# 2014_FDP_STRATEGIE.net
KiCad netlist of a schematic drawn in Altium Designer
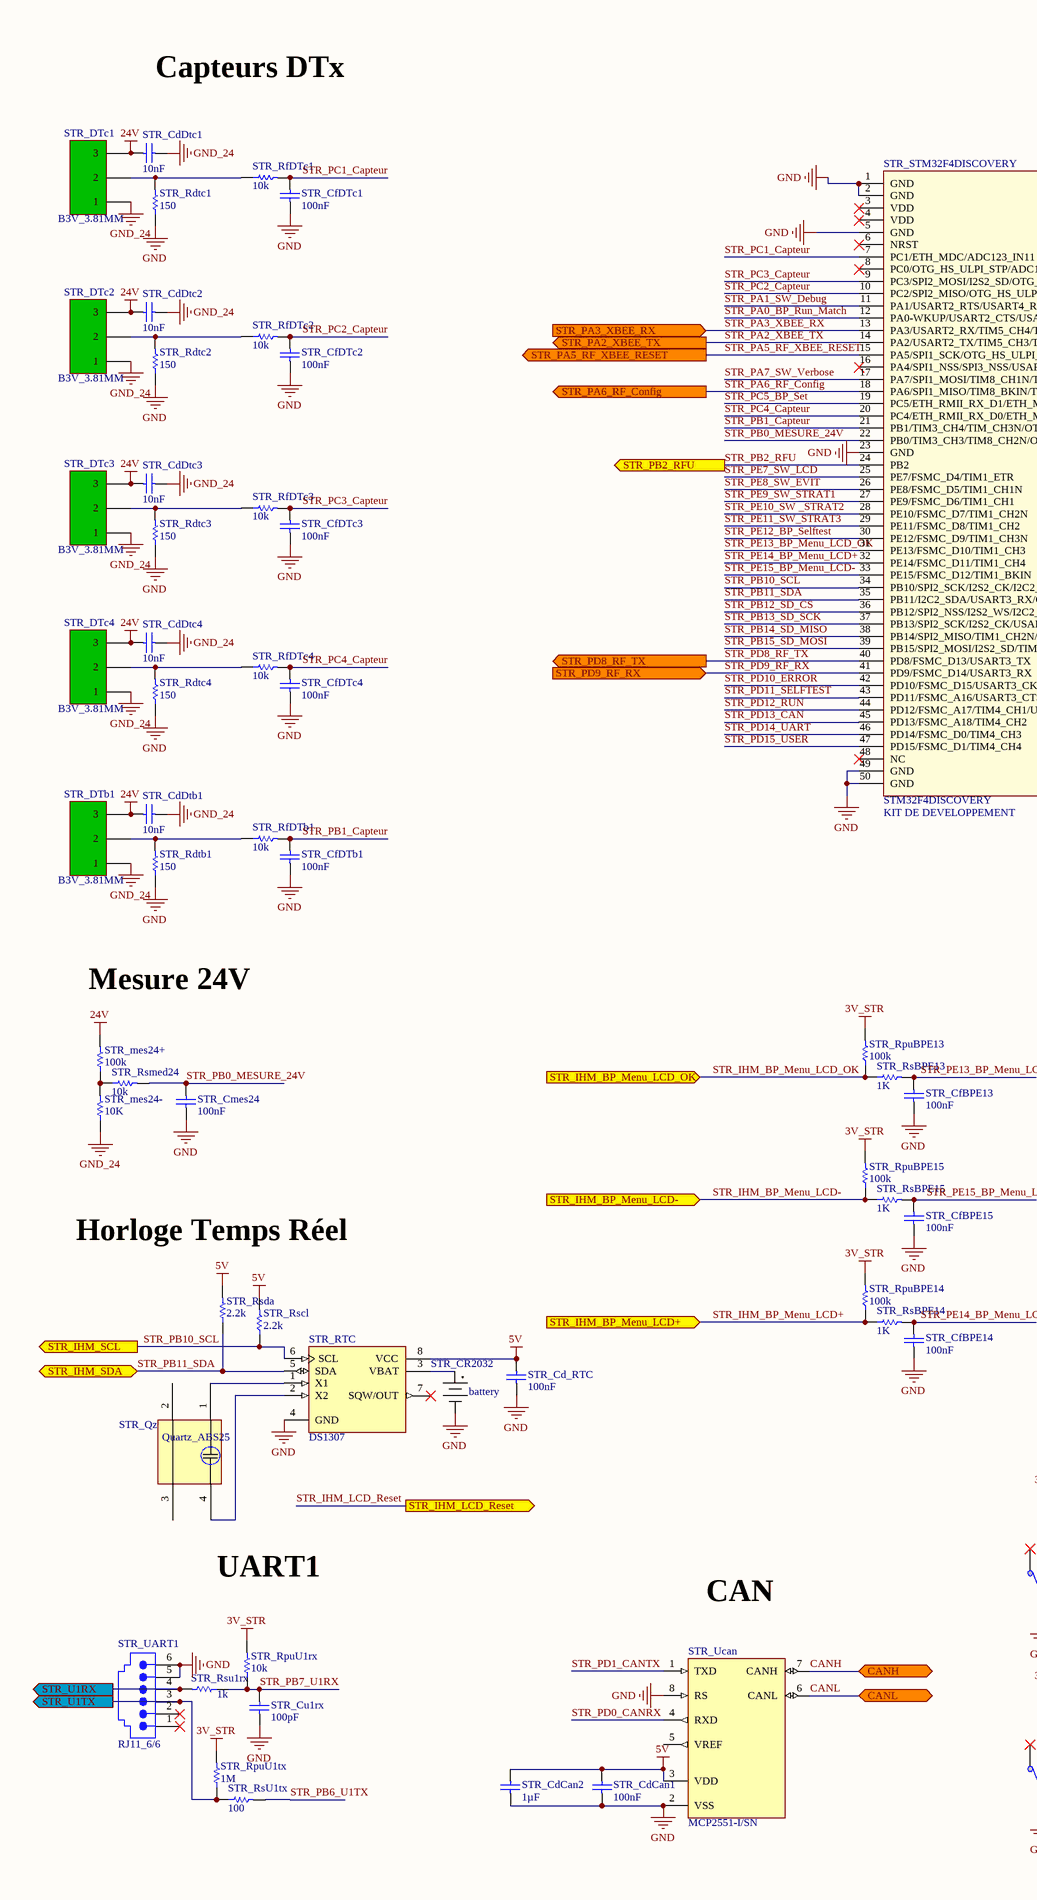
[diagram p0: 2014_FDP_STRATEGIE.SchDoc, left]
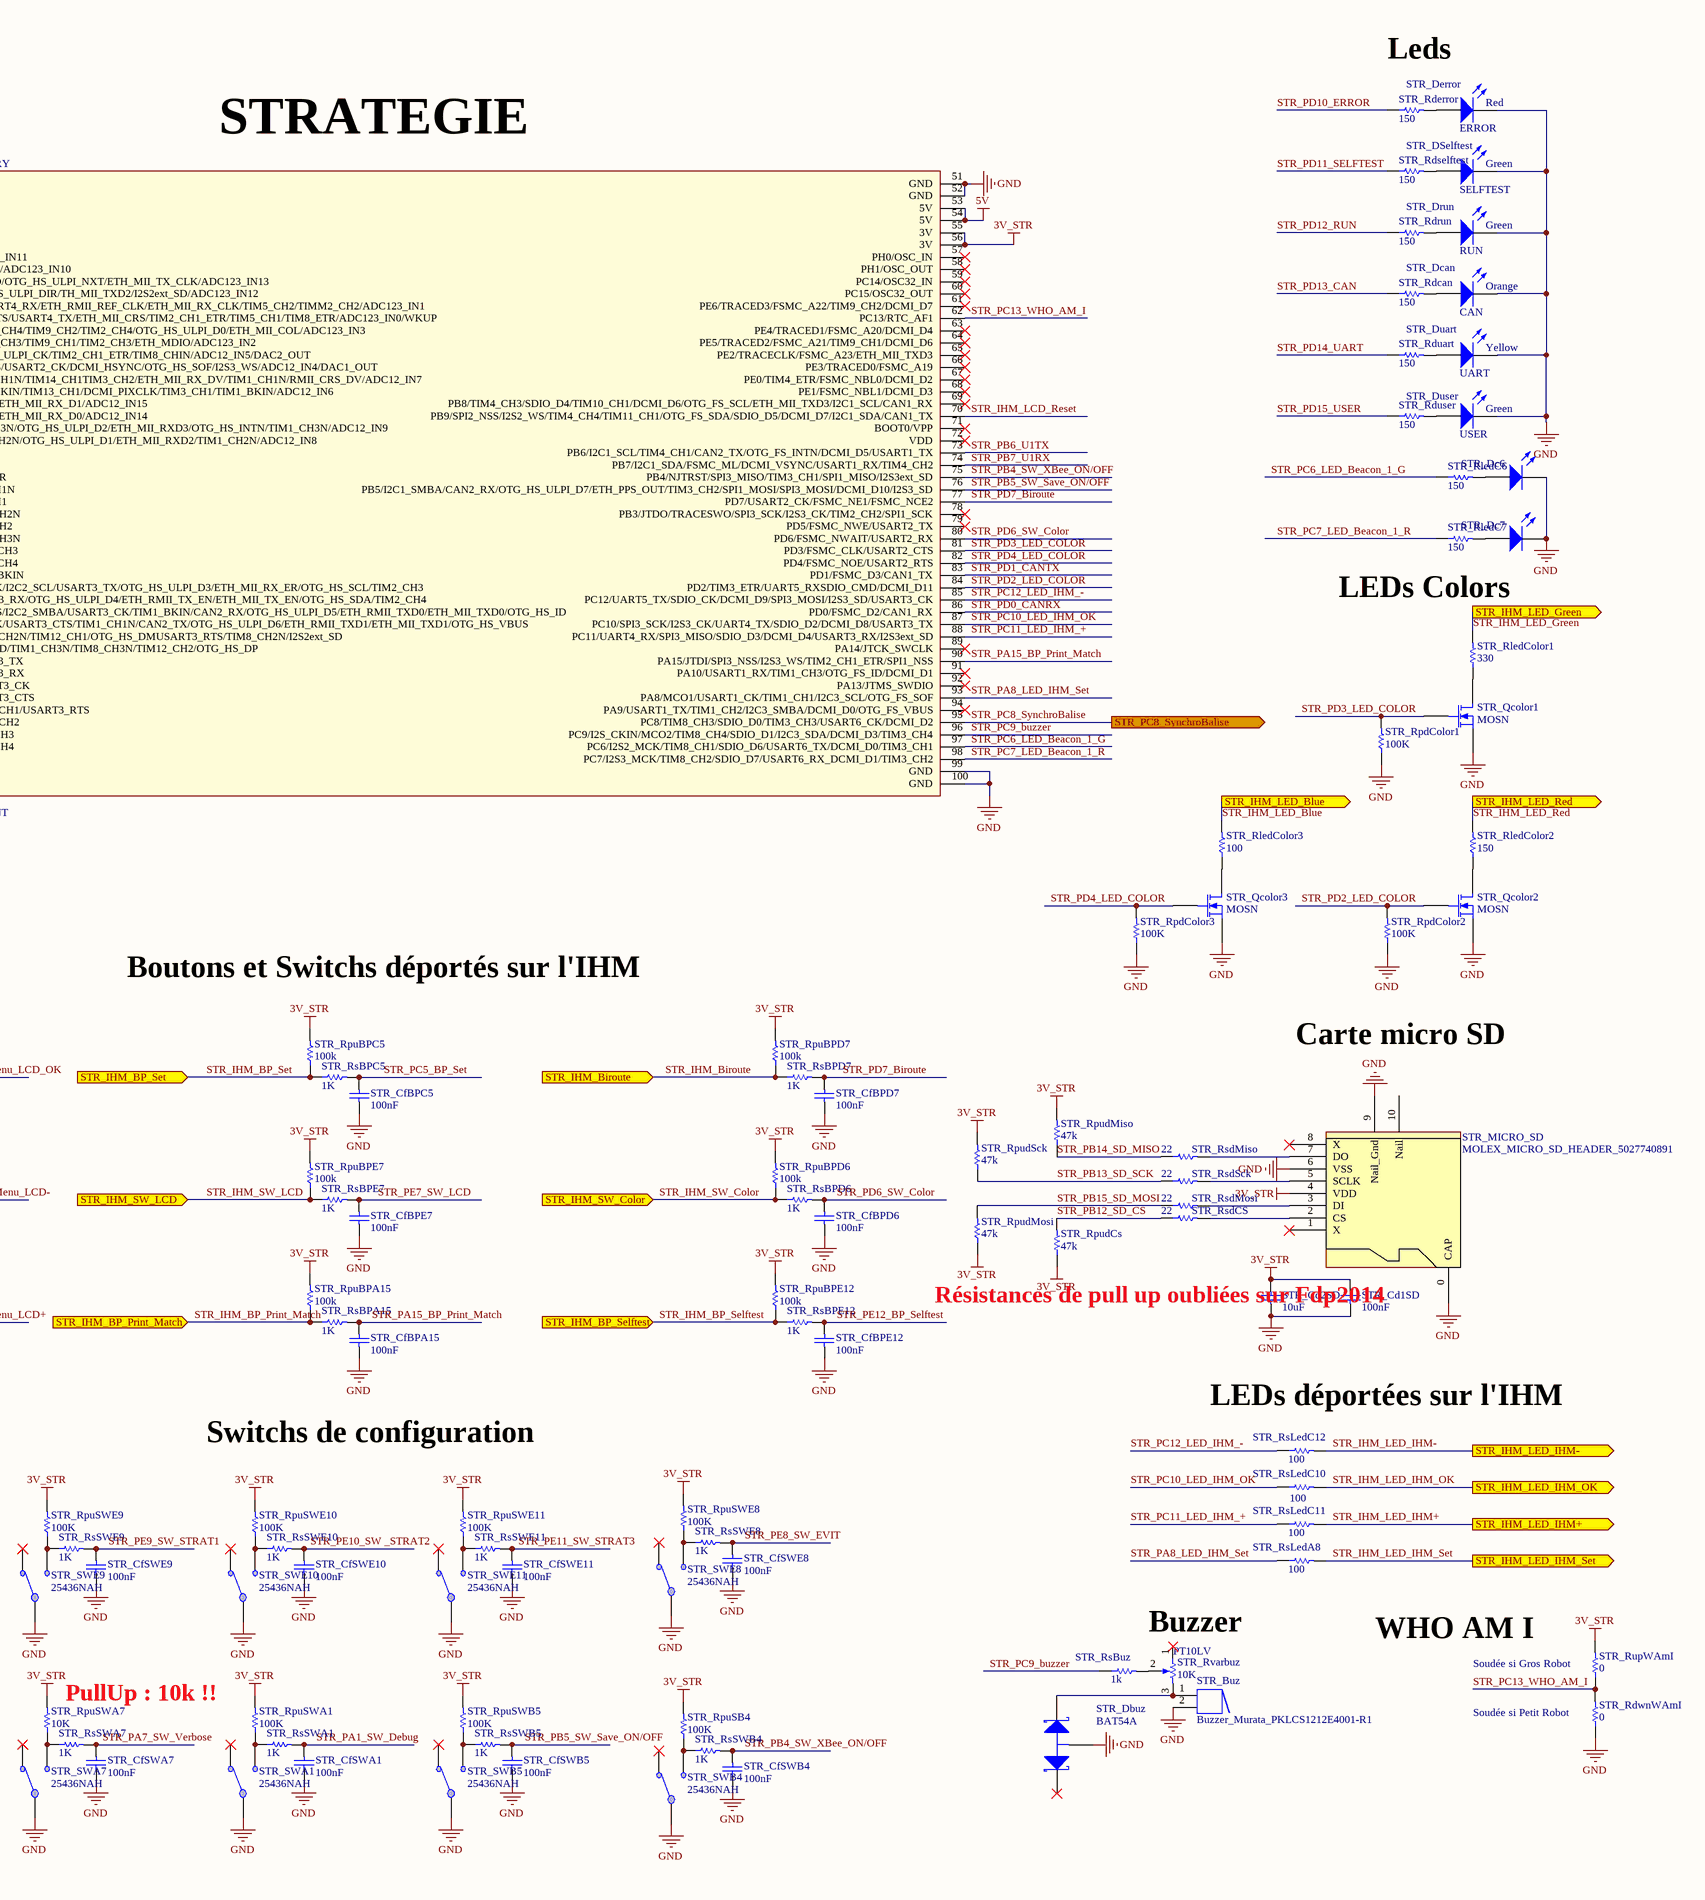
[diagram p1: 2014_FDP_STRATEGIE.SchDoc, right]

(export (version "E")
  (design (tool "Eeschema 10.0.6"))
  (components
    (comp (ref "STR_Buz")
      (value "Buzzer_Murata_PKLCS1212E4001-R1")
      (footprint "Buzzer_Murata PKLCS1212")
      (fields
        (field (name "MANUFACTURER") "MURATA")
        (field (name "MANUFACTURER PART NUMBER") "PKLCS1212E4001-R1")
      )
      (libsource (lib "DG_Buzzer") (part "Buzzer_Murata_PKLCS1212E4001-R1"))
    )
    (comp (ref "STR_Cd1SD")
      (value "100nF")
      (footprint "C0805_N")
      (description "Capacitor")
      (fields (field (name "PUBLISHER") "Altium Limited"))
      (libsource (lib "_ROBOT") (part "Condensateur"))
    )
    (comp (ref "STR_Cd2SD")
      (value "10uF")
      (footprint "C1206_N")
      (description "Capacitor")
      (fields (field (name "PUBLISHER") "Altium Limited"))
      (libsource (lib "_ROBOT") (part "Condensateur"))
    )
    (comp (ref "STR_CdCan1")
      (value "100nF")
      (footprint "C0805_N")
      (description "Capacitor")
      (fields (field (name "PUBLISHER") "Altium Limited"))
      (libsource (lib "_ROBOT") (part "Condensateur"))
    )
    (comp (ref "STR_CdCan2")
      (value "1µF")
      (footprint "C0805_N")
      (description "Capacitor")
      (fields (field (name "PUBLISHER") "Altium Limited"))
      (libsource (lib "_ROBOT") (part "Condensateur"))
    )
    (comp (ref "STR_CdDtb1")
      (value "10nF")
      (footprint "C0805_N")
      (description "Capacitor")
      (fields (field (name "PUBLISHER") "Altium Limited"))
      (libsource (lib "_ROBOT") (part "Condensateur"))
    )
    (comp (ref "STR_CdDtc1")
      (value "10nF")
      (footprint "C0805_N")
      (description "Capacitor")
      (fields (field (name "PUBLISHER") "Altium Limited"))
      (libsource (lib "_ROBOT") (part "Condensateur"))
    )
    (comp (ref "STR_CdDtc2")
      (value "10nF")
      (footprint "C0805_N")
      (description "Capacitor")
      (fields (field (name "PUBLISHER") "Altium Limited"))
      (libsource (lib "_ROBOT") (part "Condensateur"))
    )
    (comp (ref "STR_CdDtc3")
      (value "10nF")
      (footprint "C0805_N")
      (description "Capacitor")
      (fields (field (name "PUBLISHER") "Altium Limited"))
      (libsource (lib "_ROBOT") (part "Condensateur"))
    )
    (comp (ref "STR_CdDtc4")
      (value "10nF")
      (footprint "C0805_N")
      (description "Capacitor")
      (fields (field (name "PUBLISHER") "Altium Limited"))
      (libsource (lib "_ROBOT") (part "Condensateur"))
    )
    (comp (ref "STR_Cd_RTC")
      (value "100nF")
      (footprint "C0805_N")
      (description "Capacitor")
      (fields (field (name "PUBLISHER") "Altium Limited"))
      (libsource (lib "_ROBOT") (part "Condensateur"))
    )
    (comp (ref "STR_CfBPA15")
      (value "100nF")
      (footprint "C0805_N")
      (description "Capacitor")
      (fields (field (name "PUBLISHER") "Altium Limited"))
      (libsource (lib "_ROBOT") (part "Condensateur"))
    )
    (comp (ref "STR_CfBPC5")
      (value "100nF")
      (footprint "C0805_N")
      (description "Capacitor")
      (fields (field (name "PUBLISHER") "Altium Limited"))
      (libsource (lib "_ROBOT") (part "Condensateur"))
    )
    (comp (ref "STR_CfBPD6")
      (value "100nF")
      (footprint "C0805_N")
      (description "Capacitor")
      (fields (field (name "PUBLISHER") "Altium Limited"))
      (libsource (lib "_ROBOT") (part "Condensateur"))
    )
    (comp (ref "STR_CfBPD7")
      (value "100nF")
      (footprint "C0805_N")
      (description "Capacitor")
      (fields (field (name "PUBLISHER") "Altium Limited"))
      (libsource (lib "_ROBOT") (part "Condensateur"))
    )
    (comp (ref "STR_CfBPE7")
      (value "100nF")
      (footprint "C0805_N")
      (description "Capacitor")
      (fields (field (name "PUBLISHER") "Altium Limited"))
      (libsource (lib "_ROBOT") (part "Condensateur"))
    )
    (comp (ref "STR_CfBPE12")
      (value "100nF")
      (footprint "C0805_N")
      (description "Capacitor")
      (fields (field (name "PUBLISHER") "Altium Limited"))
      (libsource (lib "_ROBOT") (part "Condensateur"))
    )
    (comp (ref "STR_CfBPE13")
      (value "100nF")
      (footprint "C0805_N")
      (description "Capacitor")
      (fields (field (name "PUBLISHER") "Altium Limited"))
      (libsource (lib "_ROBOT") (part "Condensateur"))
    )
    (comp (ref "STR_CfBPE14")
      (value "100nF")
      (footprint "C0805_N")
      (description "Capacitor")
      (fields (field (name "PUBLISHER") "Altium Limited"))
      (libsource (lib "_ROBOT") (part "Condensateur"))
    )
    (comp (ref "STR_CfBPE15")
      (value "100nF")
      (footprint "C0805_N")
      (description "Capacitor")
      (fields (field (name "PUBLISHER") "Altium Limited"))
      (libsource (lib "_ROBOT") (part "Condensateur"))
    )
    (comp (ref "STR_CfDTb1")
      (value "100nF")
      (footprint "C0805_N")
      (description "Capacitor")
      (fields (field (name "PUBLISHER") "Altium Limited"))
      (libsource (lib "_ROBOT") (part "Condensateur"))
    )
    (comp (ref "STR_CfDTc1")
      (value "100nF")
      (footprint "C0805_N")
      (description "Capacitor")
      (fields (field (name "PUBLISHER") "Altium Limited"))
      (libsource (lib "_ROBOT") (part "Condensateur"))
    )
    (comp (ref "STR_CfDTc2")
      (value "100nF")
      (footprint "C0805_N")
      (description "Capacitor")
      (fields (field (name "PUBLISHER") "Altium Limited"))
      (libsource (lib "_ROBOT") (part "Condensateur"))
    )
    (comp (ref "STR_CfDTc3")
      (value "100nF")
      (footprint "C0805_N")
      (description "Capacitor")
      (fields (field (name "PUBLISHER") "Altium Limited"))
      (libsource (lib "_ROBOT") (part "Condensateur"))
    )
    (comp (ref "STR_CfDTc4")
      (value "100nF")
      (footprint "C0805_N")
      (description "Capacitor")
      (fields (field (name "PUBLISHER") "Altium Limited"))
      (libsource (lib "_ROBOT") (part "Condensateur"))
    )
    (comp (ref "STR_CfSWA1")
      (value "100nF")
      (footprint "C0805_N")
      (description "Capacitor")
      (fields (field (name "PUBLISHER") "Altium Limited"))
      (libsource (lib "_ROBOT") (part "Condensateur"))
    )
    (comp (ref "STR_CfSWA7")
      (value "100nF")
      (footprint "C0805_N")
      (description "Capacitor")
      (fields (field (name "PUBLISHER") "Altium Limited"))
      (libsource (lib "_ROBOT") (part "Condensateur"))
    )
    (comp (ref "STR_CfSWB4")
      (value "100nF")
      (footprint "C0805_N")
      (description "Capacitor")
      (fields (field (name "PUBLISHER") "Altium Limited"))
      (libsource (lib "_ROBOT") (part "Condensateur"))
    )
    (comp (ref "STR_CfSWB5")
      (value "100nF")
      (footprint "C0805_N")
      (description "Capacitor")
      (fields (field (name "PUBLISHER") "Altium Limited"))
      (libsource (lib "_ROBOT") (part "Condensateur"))
    )
    (comp (ref "STR_CfSWE8")
      (value "100nF")
      (footprint "C0805_N")
      (description "Capacitor")
      (fields (field (name "PUBLISHER") "Altium Limited"))
      (libsource (lib "_ROBOT") (part "Condensateur"))
    )
    (comp (ref "STR_CfSWE9")
      (value "100nF")
      (footprint "C0805_N")
      (description "Capacitor")
      (fields (field (name "PUBLISHER") "Altium Limited"))
      (libsource (lib "_ROBOT") (part "Condensateur"))
    )
    (comp (ref "STR_CfSWE10")
      (value "100nF")
      (footprint "C0805_N")
      (description "Capacitor")
      (fields (field (name "PUBLISHER") "Altium Limited"))
      (libsource (lib "_ROBOT") (part "Condensateur"))
    )
    (comp (ref "STR_CfSWE11")
      (value "100nF")
      (footprint "C0805_N")
      (description "Capacitor")
      (fields (field (name "PUBLISHER") "Altium Limited"))
      (libsource (lib "_ROBOT") (part "Condensateur"))
    )
    (comp (ref "STR_Cmes24")
      (value "100nF")
      (footprint "C0805_N")
      (description "Capacitor")
      (fields (field (name "PUBLISHER") "Altium Limited"))
      (libsource (lib "_ROBOT") (part "Condensateur"))
    )
    (comp (ref "STR_CR2032")
      (value "battery")
      (footprint "Pile_boutton")
      (description "Battery, Pile")
      (fields (field (name "PUBLISHER") "Jean-Philippe Oudet"))
      (libsource (lib "LibPocketTag") (part "battery"))
    )
    (comp (ref "STR_Cu1rx")
      (value "100pF")
      (footprint "C0805_N")
      (description "Capacitor")
      (fields (field (name "PUBLISHER") "Altium Limited"))
      (libsource (lib "_ROBOT") (part "Condensateur"))
    )
    (comp (ref "STR_Dbuz")
      (value "BAT54A")
      (footprint "SOT23-3N")
      (description "ZETEX - BAT54A - DIODE SCHOTTKY DOUBLE")
      (fields (field (name "MANUFACTURER") "ZETEX"))
      (libsource (lib "_ROBOT") (part "Diode Shottky double  BAT54A"))
    )
    (comp (ref "STR_Dc6")
      (value "??")
      (footprint "LED_0805")
      (description "Typical LED")
      (fields (field (name "PUBLISHER") "Altium Limited"))
      (libsource (lib "_ROBOT") (part "LED"))
    )
    (comp (ref "STR_Dc7")
      (value "??")
      (footprint "LED_0805")
      (description "Typical LED")
      (fields (field (name "PUBLISHER") "Altium Limited"))
      (libsource (lib "_ROBOT") (part "LED"))
    )
    (comp (ref "STR_Dcan")
      (value "CAN")
      (footprint "LED_0805")
      (description "Typical LED")
      (fields (field (name "PUBLISHER") "Altium Limited"))
      (libsource (lib "_ROBOT") (part "LED"))
    )
    (comp (ref "STR_Derror")
      (value "ERROR")
      (footprint "LED_0805")
      (description "Typical LED")
      (fields (field (name "PUBLISHER") "Altium Limited"))
      (libsource (lib "_ROBOT") (part "LED"))
    )
    (comp (ref "STR_Drun")
      (value "RUN")
      (footprint "LED_0805")
      (description "Typical LED")
      (fields (field (name "PUBLISHER") "Altium Limited"))
      (libsource (lib "_ROBOT") (part "LED"))
    )
    (comp (ref "STR_DSelftest")
      (value "SELFTEST")
      (footprint "LED_0805")
      (description "Typical LED")
      (fields (field (name "PUBLISHER") "Altium Limited"))
      (libsource (lib "_ROBOT") (part "LED"))
    )
    (comp (ref "STR_DTb1")
      (value "B3V_3.81MM")
      (footprint "BORNIER_3V_3.81MM")
      (libsource (lib "Connecteur") (part "BORNIER_3V_3.81MM"))
    )
    (comp (ref "STR_DTc1")
      (value "B3V_3.81MM")
      (footprint "BORNIER_3V_3.81MM")
      (libsource (lib "Connecteur") (part "BORNIER_3V_3.81MM"))
    )
    (comp (ref "STR_DTc2")
      (value "B3V_3.81MM")
      (footprint "BORNIER_3V_3.81MM")
      (libsource (lib "Connecteur") (part "BORNIER_3V_3.81MM"))
    )
    (comp (ref "STR_DTc3")
      (value "B3V_3.81MM")
      (footprint "BORNIER_3V_3.81MM")
      (libsource (lib "Connecteur") (part "BORNIER_3V_3.81MM"))
    )
    (comp (ref "STR_DTc4")
      (value "B3V_3.81MM")
      (footprint "BORNIER_3V_3.81MM")
      (libsource (lib "Connecteur") (part "BORNIER_3V_3.81MM"))
    )
    (comp (ref "STR_Duart")
      (value "UART")
      (footprint "LED_0805")
      (description "Typical LED")
      (fields (field (name "PUBLISHER") "Altium Limited"))
      (libsource (lib "_ROBOT") (part "LED"))
    )
    (comp (ref "STR_Duser")
      (value "USER")
      (footprint "LED_0805")
      (description "Typical LED")
      (fields (field (name "PUBLISHER") "Altium Limited"))
      (libsource (lib "_ROBOT") (part "LED"))
    )
    (comp (ref "STR_mes24+")
      (value "100k")
      (footprint "R1206_N")
      (description "Resistor")
      (fields (field (name "PUBLISHER") "Altium Limited"))
      (libsource (lib "_ROBOT") (part "Resistor"))
    )
    (comp (ref "STR_mes24-")
      (value "10K")
      (footprint "R1206_N")
      (description "Resistor")
      (fields (field (name "PUBLISHER") "Altium Limited"))
      (libsource (lib "_ROBOT") (part "Resistor"))
    )
    (comp (ref "STR_MICRO_SD")
      (value "MOLEX_MICRO_SD_HEADER_5027740891")
      (footprint "MOLEX_MICRO_SD_HEADER_5027740891")
      (libsource (lib "Connecteur") (part "MOLEX_MICRO_SD_HEADER_5027740891"))
    )
    (comp (ref "STR_Qcolor1")
      (value "MOSN")
      (footprint "SOT23-3N")
      (description "N-Channel MOSFET")
      (fields (field (name "PUBLISHER") "Altium Limited"))
      (libsource (lib "_ROBOT") (part "Transistor MOSFET-N"))
    )
    (comp (ref "STR_Qcolor2")
      (value "MOSN")
      (footprint "SOT23-3N")
      (description "N-Channel MOSFET")
      (fields (field (name "PUBLISHER") "Altium Limited"))
      (libsource (lib "_ROBOT") (part "Transistor MOSFET-N"))
    )
    (comp (ref "STR_Qcolor3")
      (value "MOSN")
      (footprint "SOT23-3N")
      (description "N-Channel MOSFET")
      (fields (field (name "PUBLISHER") "Altium Limited"))
      (libsource (lib "_ROBOT") (part "Transistor MOSFET-N"))
    )
    (comp (ref "STR_Qz")
      (value "Quartz_ABS25")
      (footprint "Quartz_ABS25")
      (libsource (lib "_ROBOT") (part "Quartz_ABS25"))
    )
    (comp (ref "STR_Rdcan")
      (value "150")
      (footprint "R1206_N")
      (description "Resistor")
      (fields (field (name "PUBLISHER") "Altium Limited"))
      (libsource (lib "_ROBOT") (part "Resistor"))
    )
    (comp (ref "STR_Rderror")
      (value "150")
      (footprint "R1206_N")
      (description "Resistor")
      (fields (field (name "PUBLISHER") "Altium Limited"))
      (libsource (lib "_ROBOT") (part "Resistor"))
    )
    (comp (ref "STR_Rdrun")
      (value "150")
      (footprint "R1206_N")
      (description "Resistor")
      (fields (field (name "PUBLISHER") "Altium Limited"))
      (libsource (lib "_ROBOT") (part "Resistor"))
    )
    (comp (ref "STR_Rdselftest")
      (value "150")
      (footprint "R1206_N")
      (description "Resistor")
      (fields (field (name "PUBLISHER") "Altium Limited"))
      (libsource (lib "_ROBOT") (part "Resistor"))
    )
    (comp (ref "STR_Rdtb1")
      (value "150")
      (footprint "R1206_N")
      (description "Resistor")
      (fields (field (name "PUBLISHER") "Altium Limited"))
      (libsource (lib "_ROBOT") (part "Resistor"))
    )
    (comp (ref "STR_Rdtc1")
      (value "150")
      (footprint "R1206_N")
      (description "Resistor")
      (fields (field (name "PUBLISHER") "Altium Limited"))
      (libsource (lib "_ROBOT") (part "Resistor"))
    )
    (comp (ref "STR_Rdtc2")
      (value "150")
      (footprint "R1206_N")
      (description "Resistor")
      (fields (field (name "PUBLISHER") "Altium Limited"))
      (libsource (lib "_ROBOT") (part "Resistor"))
    )
    (comp (ref "STR_Rdtc3")
      (value "150")
      (footprint "R1206_N")
      (description "Resistor")
      (fields (field (name "PUBLISHER") "Altium Limited"))
      (libsource (lib "_ROBOT") (part "Resistor"))
    )
    (comp (ref "STR_Rdtc4")
      (value "150")
      (footprint "R1206_N")
      (description "Resistor")
      (fields (field (name "PUBLISHER") "Altium Limited"))
      (libsource (lib "_ROBOT") (part "Resistor"))
    )
    (comp (ref "STR_Rduart")
      (value "150")
      (footprint "R1206_N")
      (description "Resistor")
      (fields (field (name "PUBLISHER") "Altium Limited"))
      (libsource (lib "_ROBOT") (part "Resistor"))
    )
    (comp (ref "STR_Rduser")
      (value "150")
      (footprint "R1206_N")
      (description "Resistor")
      (fields (field (name "PUBLISHER") "Altium Limited"))
      (libsource (lib "_ROBOT") (part "Resistor"))
    )
    (comp (ref "STR_RdwnWAmI")
      (value "0")
      (footprint "R1206_N")
      (description "Resistor")
      (fields (field (name "PUBLISHER") "Altium Limited"))
      (libsource (lib "_ROBOT") (part "Resistor"))
    )
    (comp (ref "STR_RfDTb1")
      (value "10k")
      (footprint "R1206_N")
      (description "Resistor")
      (fields (field (name "PUBLISHER") "Altium Limited"))
      (libsource (lib "_ROBOT") (part "Resistor"))
    )
    (comp (ref "STR_RfDTc1")
      (value "10k")
      (footprint "R1206_N")
      (description "Resistor")
      (fields (field (name "PUBLISHER") "Altium Limited"))
      (libsource (lib "_ROBOT") (part "Resistor"))
    )
    (comp (ref "STR_RfDTc2")
      (value "10k")
      (footprint "R1206_N")
      (description "Resistor")
      (fields (field (name "PUBLISHER") "Altium Limited"))
      (libsource (lib "_ROBOT") (part "Resistor"))
    )
    (comp (ref "STR_RfDTc3")
      (value "10k")
      (footprint "R1206_N")
      (description "Resistor")
      (fields (field (name "PUBLISHER") "Altium Limited"))
      (libsource (lib "_ROBOT") (part "Resistor"))
    )
    (comp (ref "STR_RfDTc4")
      (value "10k")
      (footprint "R1206_N")
      (description "Resistor")
      (fields (field (name "PUBLISHER") "Altium Limited"))
      (libsource (lib "_ROBOT") (part "Resistor"))
    )
    (comp (ref "STR_RledC6")
      (value "150")
      (footprint "R1206_N")
      (description "Resistor")
      (fields (field (name "PUBLISHER") "Altium Limited"))
      (libsource (lib "_ROBOT") (part "Resistor"))
    )
    (comp (ref "STR_RledC7")
      (value "150")
      (footprint "R1206_N")
      (description "Resistor")
      (fields (field (name "PUBLISHER") "Altium Limited"))
      (libsource (lib "_ROBOT") (part "Resistor"))
    )
    (comp (ref "STR_RledColor1")
      (value "330")
      (footprint "R1206_N")
      (description "Resistor")
      (fields (field (name "PUBLISHER") "Altium Limited"))
      (libsource (lib "_ROBOT") (part "Resistor"))
    )
    (comp (ref "STR_RledColor2")
      (value "150")
      (footprint "R1206_N")
      (description "Resistor")
      (fields (field (name "PUBLISHER") "Altium Limited"))
      (libsource (lib "_ROBOT") (part "Resistor"))
    )
    (comp (ref "STR_RledColor3")
      (value "100")
      (footprint "R1206_N")
      (description "Resistor")
      (fields (field (name "PUBLISHER") "Altium Limited"))
      (libsource (lib "_ROBOT") (part "Resistor"))
    )
    (comp (ref "STR_RpdColor1")
      (value "100K")
      (footprint "R1206_N")
      (description "Resistor")
      (fields (field (name "PUBLISHER") "Altium Limited"))
      (libsource (lib "_ROBOT") (part "Resistor"))
    )
    (comp (ref "STR_RpdColor2")
      (value "100K")
      (footprint "R1206_N")
      (description "Resistor")
      (fields (field (name "PUBLISHER") "Altium Limited"))
      (libsource (lib "_ROBOT") (part "Resistor"))
    )
    (comp (ref "STR_RpdColor3")
      (value "100K")
      (footprint "R1206_N")
      (description "Resistor")
      (fields (field (name "PUBLISHER") "Altium Limited"))
      (libsource (lib "_ROBOT") (part "Resistor"))
    )
    (comp (ref "STR_RpuBPA15")
      (value "100k")
      (footprint "R1206_N")
      (description "Resistor")
      (fields (field (name "PUBLISHER") "Altium Limited"))
      (libsource (lib "_ROBOT") (part "Resistor"))
    )
    (comp (ref "STR_RpuBPC5")
      (value "100k")
      (footprint "R1206_N")
      (description "Resistor")
      (fields (field (name "PUBLISHER") "Altium Limited"))
      (libsource (lib "_ROBOT") (part "Resistor"))
    )
    (comp (ref "STR_RpuBPD6")
      (value "100k")
      (footprint "R1206_N")
      (description "Resistor")
      (fields (field (name "PUBLISHER") "Altium Limited"))
      (libsource (lib "_ROBOT") (part "Resistor"))
    )
    (comp (ref "STR_RpuBPD7")
      (value "100k")
      (footprint "R1206_N")
      (description "Resistor")
      (fields (field (name "PUBLISHER") "Altium Limited"))
      (libsource (lib "_ROBOT") (part "Resistor"))
    )
    (comp (ref "STR_RpuBPE7")
      (value "100k")
      (footprint "R1206_N")
      (description "Resistor")
      (fields (field (name "PUBLISHER") "Altium Limited"))
      (libsource (lib "_ROBOT") (part "Resistor"))
    )
    (comp (ref "STR_RpuBPE12")
      (value "100k")
      (footprint "R1206_N")
      (description "Resistor")
      (fields (field (name "PUBLISHER") "Altium Limited"))
      (libsource (lib "_ROBOT") (part "Resistor"))
    )
    (comp (ref "STR_RpuBPE13")
      (value "100k")
      (footprint "R1206_N")
      (description "Resistor")
      (fields (field (name "PUBLISHER") "Altium Limited"))
      (libsource (lib "_ROBOT") (part "Resistor"))
    )
    (comp (ref "STR_RpuBPE14")
      (value "100k")
      (footprint "R1206_N")
      (description "Resistor")
      (fields (field (name "PUBLISHER") "Altium Limited"))
      (libsource (lib "_ROBOT") (part "Resistor"))
    )
    (comp (ref "STR_RpuBPE15")
      (value "100k")
      (footprint "R1206_N")
      (description "Resistor")
      (fields (field (name "PUBLISHER") "Altium Limited"))
      (libsource (lib "_ROBOT") (part "Resistor"))
    )
    (comp (ref "STR_RpudCs")
      (value "47k")
      (footprint "R1206_N")
      (description "Resistor")
      (fields (field (name "PUBLISHER") "Altium Limited"))
      (libsource (lib "_ROBOT") (part "Resistor"))
    )
    (comp (ref "STR_RpudMiso")
      (value "47k")
      (footprint "R1206_N")
      (description "Resistor")
      (fields (field (name "PUBLISHER") "Altium Limited"))
      (libsource (lib "_ROBOT") (part "Resistor"))
    )
    (comp (ref "STR_RpudMosi")
      (value "47k")
      (footprint "R1206_N")
      (description "Resistor")
      (fields (field (name "PUBLISHER") "Altium Limited"))
      (libsource (lib "_ROBOT") (part "Resistor"))
    )
    (comp (ref "STR_RpudSck")
      (value "47k")
      (footprint "R1206_N")
      (description "Resistor")
      (fields (field (name "PUBLISHER") "Altium Limited"))
      (libsource (lib "_ROBOT") (part "Resistor"))
    )
    (comp (ref "STR_RpuSB4")
      (value "100K")
      (footprint "R1206_N")
      (description "Resistor")
      (fields (field (name "PUBLISHER") "Altium Limited"))
      (libsource (lib "_ROBOT") (part "Resistor"))
    )
    (comp (ref "STR_RpuSWA1")
      (value "100K")
      (footprint "R1206_N")
      (description "Resistor")
      (fields (field (name "PUBLISHER") "Altium Limited"))
      (libsource (lib "_ROBOT") (part "Resistor"))
    )
    (comp (ref "STR_RpuSWA7")
      (value "10K")
      (footprint "R1206_N")
      (description "Resistor")
      (fields (field (name "PUBLISHER") "Altium Limited"))
      (libsource (lib "_ROBOT") (part "Resistor"))
    )
    (comp (ref "STR_RpuSWB5")
      (value "100K")
      (footprint "R1206_N")
      (description "Resistor")
      (fields (field (name "PUBLISHER") "Altium Limited"))
      (libsource (lib "_ROBOT") (part "Resistor"))
    )
    (comp (ref "STR_RpuSWE8")
      (value "100K")
      (footprint "R1206_N")
      (description "Resistor")
      (fields (field (name "PUBLISHER") "Altium Limited"))
      (libsource (lib "_ROBOT") (part "Resistor"))
    )
    (comp (ref "STR_RpuSWE9")
      (value "100K")
      (footprint "R1206_N")
      (description "Resistor")
      (fields (field (name "PUBLISHER") "Altium Limited"))
      (libsource (lib "_ROBOT") (part "Resistor"))
    )
    (comp (ref "STR_RpuSWE10")
      (value "100K")
      (footprint "R1206_N")
      (description "Resistor")
      (fields (field (name "PUBLISHER") "Altium Limited"))
      (libsource (lib "_ROBOT") (part "Resistor"))
    )
    (comp (ref "STR_RpuSWE11")
      (value "100K")
      (footprint "R1206_N")
      (description "Resistor")
      (fields (field (name "PUBLISHER") "Altium Limited"))
      (libsource (lib "_ROBOT") (part "Resistor"))
    )
    (comp (ref "STR_RpuU1rx")
      (value "10k")
      (footprint "R1206_N")
      (description "Resistor")
      (fields (field (name "PUBLISHER") "Altium Limited"))
      (libsource (lib "_ROBOT") (part "Resistor"))
    )
    (comp (ref "STR_RpuU1tx")
      (value "1M")
      (footprint "R1206_N")
      (description "Resistor")
      (fields (field (name "PUBLISHER") "Altium Limited"))
      (libsource (lib "_ROBOT") (part "Resistor"))
    )
    (comp (ref "STR_RsBPA15")
      (value "1K")
      (footprint "R1206_N")
      (description "Resistor")
      (fields (field (name "PUBLISHER") "Altium Limited"))
      (libsource (lib "_ROBOT") (part "Resistor"))
    )
    (comp (ref "STR_RsBPC5")
      (value "1K")
      (footprint "R1206_N")
      (description "Resistor")
      (fields (field (name "PUBLISHER") "Altium Limited"))
      (libsource (lib "_ROBOT") (part "Resistor"))
    )
    (comp (ref "STR_RsBPD6")
      (value "1K")
      (footprint "R1206_N")
      (description "Resistor")
      (fields (field (name "PUBLISHER") "Altium Limited"))
      (libsource (lib "_ROBOT") (part "Resistor"))
    )
    (comp (ref "STR_RsBPD7")
      (value "1K")
      (footprint "R1206_N")
      (description "Resistor")
      (fields (field (name "PUBLISHER") "Altium Limited"))
      (libsource (lib "_ROBOT") (part "Resistor"))
    )
    (comp (ref "STR_RsBPE7")
      (value "1K")
      (footprint "R1206_N")
      (description "Resistor")
      (fields (field (name "PUBLISHER") "Altium Limited"))
      (libsource (lib "_ROBOT") (part "Resistor"))
    )
    (comp (ref "STR_RsBPE12")
      (value "1K")
      (footprint "R1206_N")
      (description "Resistor")
      (fields (field (name "PUBLISHER") "Altium Limited"))
      (libsource (lib "_ROBOT") (part "Resistor"))
    )
    (comp (ref "STR_RsBPE13")
      (value "1K")
      (footprint "R1206_N")
      (description "Resistor")
      (fields (field (name "PUBLISHER") "Altium Limited"))
      (libsource (lib "_ROBOT") (part "Resistor"))
    )
    (comp (ref "STR_RsBPE14")
      (value "1K")
      (footprint "R1206_N")
      (description "Resistor")
      (fields (field (name "PUBLISHER") "Altium Limited"))
      (libsource (lib "_ROBOT") (part "Resistor"))
    )
    (comp (ref "STR_RsBPE15")
      (value "1K")
      (footprint "R1206_N")
      (description "Resistor")
      (fields (field (name "PUBLISHER") "Altium Limited"))
      (libsource (lib "_ROBOT") (part "Resistor"))
    )
    (comp (ref "STR_RsBuz")
      (value "1k")
      (footprint "R1206_N")
      (description "Resistor")
      (fields (field (name "PUBLISHER") "Altium Limited"))
      (libsource (lib "_ROBOT") (part "Resistor"))
    )
    (comp (ref "STR_Rscl")
      (value "2.2k")
      (footprint "R1206_N")
      (description "Resistor")
      (fields (field (name "PUBLISHER") "Altium Limited"))
      (libsource (lib "_ROBOT") (part "Resistor"))
    )
    (comp (ref "STR_Rsda")
      (value "2.2k")
      (footprint "R1206_N")
      (description "Resistor")
      (fields (field (name "PUBLISHER") "Altium Limited"))
      (libsource (lib "_ROBOT") (part "Resistor"))
    )
    (comp (ref "STR_RsdCS")
      (value "22")
      (footprint "R1206_N")
      (description "Resistor")
      (fields (field (name "PUBLISHER") "Altium Limited"))
      (libsource (lib "_ROBOT") (part "Resistor"))
    )
    (comp (ref "STR_RsdMiso")
      (value "22")
      (footprint "R1206_N")
      (description "Resistor")
      (fields (field (name "PUBLISHER") "Altium Limited"))
      (libsource (lib "_ROBOT") (part "Resistor"))
    )
    (comp (ref "STR_RsdMosi")
      (value "22")
      (footprint "R1206_N")
      (description "Resistor")
      (fields (field (name "PUBLISHER") "Altium Limited"))
      (libsource (lib "_ROBOT") (part "Resistor"))
    )
    (comp (ref "STR_RsdSck")
      (value "22")
      (footprint "R1206_N")
      (description "Resistor")
      (fields (field (name "PUBLISHER") "Altium Limited"))
      (libsource (lib "_ROBOT") (part "Resistor"))
    )
    (comp (ref "STR_RsLedA8")
      (value "100")
      (footprint "R1206_N")
      (description "Resistor")
      (fields (field (name "PUBLISHER") "Altium Limited"))
      (libsource (lib "_ROBOT") (part "Resistor"))
    )
    (comp (ref "STR_RsLedC10")
      (value "100")
      (footprint "R1206_N")
      (description "Resistor")
      (fields (field (name "PUBLISHER") "Altium Limited"))
      (libsource (lib "_ROBOT") (part "Resistor"))
    )
    (comp (ref "STR_RsLedC11")
      (value "100")
      (footprint "R1206_N")
      (description "Resistor")
      (fields (field (name "PUBLISHER") "Altium Limited"))
      (libsource (lib "_ROBOT") (part "Resistor"))
    )
    (comp (ref "STR_RsLedC12")
      (value "100")
      (footprint "R1206_N")
      (description "Resistor")
      (fields (field (name "PUBLISHER") "Altium Limited"))
      (libsource (lib "_ROBOT") (part "Resistor"))
    )
    (comp (ref "STR_Rsmed24")
      (value "10k")
      (footprint "R1206_N")
      (description "Resistor")
      (fields (field (name "PUBLISHER") "Altium Limited"))
      (libsource (lib "_ROBOT") (part "Resistor"))
    )
    (comp (ref "STR_RsSWA1")
      (value "1K")
      (footprint "R1206_N")
      (description "Resistor")
      (fields (field (name "PUBLISHER") "Altium Limited"))
      (libsource (lib "_ROBOT") (part "Resistor"))
    )
    (comp (ref "STR_RsSWA7")
      (value "1K")
      (footprint "R1206_N")
      (description "Resistor")
      (fields (field (name "PUBLISHER") "Altium Limited"))
      (libsource (lib "_ROBOT") (part "Resistor"))
    )
    (comp (ref "STR_RsSWB4")
      (value "1K")
      (footprint "R1206_N")
      (description "Resistor")
      (fields (field (name "PUBLISHER") "Altium Limited"))
      (libsource (lib "_ROBOT") (part "Resistor"))
    )
    (comp (ref "STR_RsSWB5")
      (value "1K")
      (footprint "R1206_N")
      (description "Resistor")
      (fields (field (name "PUBLISHER") "Altium Limited"))
      (libsource (lib "_ROBOT") (part "Resistor"))
    )
    (comp (ref "STR_RsSWE8")
      (value "1K")
      (footprint "R1206_N")
      (description "Resistor")
      (fields (field (name "PUBLISHER") "Altium Limited"))
      (libsource (lib "_ROBOT") (part "Resistor"))
    )
    (comp (ref "STR_RsSWE9")
      (value "1K")
      (footprint "R1206_N")
      (description "Resistor")
      (fields (field (name "PUBLISHER") "Altium Limited"))
      (libsource (lib "_ROBOT") (part "Resistor"))
    )
    (comp (ref "STR_RsSWE10")
      (value "1K")
      (footprint "R1206_N")
      (description "Resistor")
      (fields (field (name "PUBLISHER") "Altium Limited"))
      (libsource (lib "_ROBOT") (part "Resistor"))
    )
    (comp (ref "STR_RsSWE11")
      (value "1K")
      (footprint "R1206_N")
      (description "Resistor")
      (fields (field (name "PUBLISHER") "Altium Limited"))
      (libsource (lib "_ROBOT") (part "Resistor"))
    )
    (comp (ref "STR_Rsu1rx")
      (value "1k")
      (footprint "R1206_N")
      (description "Resistor")
      (fields (field (name "PUBLISHER") "Altium Limited"))
      (libsource (lib "_ROBOT") (part "Resistor"))
    )
    (comp (ref "STR_RsU1tx")
      (value "100")
      (footprint "R1206_N")
      (description "Resistor")
      (fields (field (name "PUBLISHER") "Altium Limited"))
      (libsource (lib "_ROBOT") (part "Resistor"))
    )
    (comp (ref "STR_RTC")
      (value "DS1307")
      (footprint "SO8_N")
      (description "64 X 8 Serial Real-Time Clock")
      (fields (field (name "PUBLISHER") "Altium Limited"))
      (libsource (lib "Robot2010") (part "DS1307"))
    )
    (comp (ref "STR_RupWAmI")
      (value "0")
      (footprint "R1206_N")
      (description "Resistor")
      (fields (field (name "PUBLISHER") "Altium Limited"))
      (libsource (lib "_ROBOT") (part "Resistor"))
    )
    (comp (ref "STR_Rvarbuz")
      (value "10K")
      (footprint "TRIMMER_MONOTOUR_PT10LV")
      (description "RESISTANCE VARIABLE_TRAVERSANTE : PT10LV")
      (fields
        (field (name "TYPE") "PT10LV")
        (field (name "Comment") "RESISTANCE_VARIABLE_TRAVERSANTE : PT10LV")
      )
      (libsource (lib "composants passifs") (part "RESISTANCE_VARIABLE_TRAVERSANTE {colon} PT10LV"))
    )
    (comp (ref "STR_STM32F4DISCOVERY")
      (value "STM32F4DISCOVERY")
      (footprint "STM32_F4DISCOVERY")
      (description "KIT DE DEVELOPPEMENT POUR MICROCONTROLEUR STM32F407VGT6")
      (fields (field (name "TYPE") "KIT DE DEVELOPPEMENT"))
      (libsource (lib "circuits integres") (part "STM32F4DISCOVERY"))
    )
    (comp (ref "STR_SWA1")
      (value "25436NAH")
      (footprint "SW_UNIPOL_DROIT - APEM 18235")
      (description "Switch unipolaire a levier")
      (libsource (lib "_ROBOT") (part "SW SPDT- APEM Série 523x"))
    )
    (comp (ref "STR_SWA7")
      (value "25436NAH")
      (footprint "SW_UNIPOL_DROIT - APEM 18235")
      (description "Switch unipolaire a levier")
      (libsource (lib "_ROBOT") (part "SW SPDT- APEM Série 523x"))
    )
    (comp (ref "STR_SWB4")
      (value "25436NAH")
      (footprint "SW_UNIPOL_DROIT - APEM 18235")
      (description "Switch unipolaire a levier")
      (libsource (lib "_ROBOT") (part "SW SPDT- APEM Série 523x"))
    )
    (comp (ref "STR_SWB5")
      (value "25436NAH")
      (footprint "SW_UNIPOL_DROIT - APEM 18235")
      (description "Switch unipolaire a levier")
      (libsource (lib "_ROBOT") (part "SW SPDT- APEM Série 523x"))
    )
    (comp (ref "STR_SWE8")
      (value "25436NAH")
      (footprint "SW_UNIPOL_DROIT - APEM 18235")
      (description "Switch unipolaire a levier")
      (libsource (lib "_ROBOT") (part "SW SPDT- APEM Série 523x"))
    )
    (comp (ref "STR_SWE9")
      (value "25436NAH")
      (footprint "SW_UNIPOL_DROIT - APEM 18235")
      (description "Switch unipolaire a levier")
      (libsource (lib "_ROBOT") (part "SW SPDT- APEM Série 523x"))
    )
    (comp (ref "STR_SWE10")
      (value "25436NAH")
      (footprint "SW_UNIPOL_DROIT - APEM 18235")
      (description "Switch unipolaire a levier")
      (libsource (lib "_ROBOT") (part "SW SPDT- APEM Série 523x"))
    )
    (comp (ref "STR_SWE11")
      (value "25436NAH")
      (footprint "SW_UNIPOL_DROIT - APEM 18235")
      (description "Switch unipolaire a levier")
      (libsource (lib "_ROBOT") (part "SW SPDT- APEM Série 523x"))
    )
    (comp (ref "STR_UART1")
      (value "RJ11_6/6")
      (footprint "RJ11_6/6")
      (description "Right Angle, Standard Profile, Offset Latch DECconnect, Flangeless PCB Jack")
      (fields (field (name "PUBLISHER") "Altium Limited"))
      (libsource (lib "Connecteur") (part "RJ11_6/6"))
    )
    (comp (ref "STR_Ucan")
      (value "MCP2551-I/SN")
      (footprint "SO8_N")
      (description "High-Speed CAN Transceiver, 8-Pin SOIC, Industrial Temperature")
      (fields (field (name "PUBLISHER") "Damien Guitton"))
      (libsource (lib "Circuit intégré") (part "MCP2551-I/SN"))
    )
  )
  (nets
    (net (code "1") (name "/CANH") (class "Default")
      (node (ref "STR_Ucan") (pin "7") (pinfunction "CANH_7") (pintype "bidirectional"))
    )
    (net (code "2") (name "/CANL") (class "Default")
      (node (ref "STR_Ucan") (pin "6") (pinfunction "CANL_6") (pintype "bidirectional"))
    )
    (net (code "3") (name "/STR_IHM_BP_Menu_LCD+") (class "Default")
      (node (ref "STR_RpuBPE14") (pin "1") (pinfunction "1_1") (pintype "passive"))
      (node (ref "STR_RsBPE14") (pin "1") (pinfunction "1_1") (pintype "passive"))
    )
    (net (code "4") (name "/STR_IHM_BP_Menu_LCD-") (class "Default")
      (node (ref "STR_RpuBPE15") (pin "1") (pinfunction "1_1") (pintype "passive"))
      (node (ref "STR_RsBPE15") (pin "1") (pinfunction "1_1") (pintype "passive"))
    )
    (net (code "5") (name "/STR_IHM_BP_Menu_LCD_OK") (class "Default")
      (node (ref "STR_RpuBPE13") (pin "1") (pinfunction "1_1") (pintype "passive"))
      (node (ref "STR_RsBPE13") (pin "1") (pinfunction "1_1") (pintype "passive"))
    )
    (net (code "6") (name "/STR_IHM_BP_Print_Match") (class "Default")
      (node (ref "STR_RpuBPA15") (pin "1") (pinfunction "1_1") (pintype "passive"))
      (node (ref "STR_RsBPA15") (pin "1") (pinfunction "1_1") (pintype "passive"))
    )
    (net (code "7") (name "/STR_IHM_BP_Selftest") (class "Default")
      (node (ref "STR_RpuBPE12") (pin "1") (pinfunction "1_1") (pintype "passive"))
      (node (ref "STR_RsBPE12") (pin "1") (pinfunction "1_1") (pintype "passive"))
    )
    (net (code "8") (name "/STR_IHM_BP_Set") (class "Default")
      (node (ref "STR_RpuBPC5") (pin "1") (pinfunction "1_1") (pintype "passive"))
      (node (ref "STR_RsBPC5") (pin "1") (pinfunction "1_1") (pintype "passive"))
    )
    (net (code "9") (name "/STR_IHM_Biroute") (class "Default")
      (node (ref "STR_RpuBPD7") (pin "1") (pinfunction "1_1") (pintype "passive"))
      (node (ref "STR_RsBPD7") (pin "1") (pinfunction "1_1") (pintype "passive"))
    )
    (net (code "10") (name "/STR_IHM_LCD_Reset") (class "Default")
      (node (ref "STR_STM32F4DISCOVERY") (pin "70") (pinfunction "PB9/SPI2_NSS/I2S2_WS/TIM4_CH4/TIM11_CH1/OTG_FS_SDA/SDIO_D5/DCMI_D7/I2C1_SDA/CAN1_TX_70") (pintype "passive"))
    )
    (net (code "11") (name "/STR_IHM_LED_Blue") (class "Default")
      (node (ref "STR_RledColor3") (pin "2") (pinfunction "2_2") (pintype "passive"))
    )
    (net (code "12") (name "/STR_IHM_LED_Green") (class "Default")
      (node (ref "STR_RledColor1") (pin "2") (pinfunction "2_2") (pintype "passive"))
    )
    (net (code "13") (name "/STR_IHM_LED_IHM+") (class "Default")
      (node (ref "STR_RsLedC11") (pin "2") (pinfunction "2_2") (pintype "passive"))
    )
    (net (code "14") (name "/STR_IHM_LED_IHM-") (class "Default")
      (node (ref "STR_RsLedC12") (pin "2") (pinfunction "2_2") (pintype "passive"))
    )
    (net (code "15") (name "/STR_IHM_LED_IHM_OK") (class "Default")
      (node (ref "STR_RsLedC10") (pin "2") (pinfunction "2_2") (pintype "passive"))
    )
    (net (code "16") (name "/STR_IHM_LED_IHM_Set") (class "Default")
      (node (ref "STR_RsLedA8") (pin "2") (pinfunction "2_2") (pintype "passive"))
    )
    (net (code "17") (name "/STR_IHM_LED_Red") (class "Default")
      (node (ref "STR_RledColor2") (pin "2") (pinfunction "2_2") (pintype "passive"))
    )
    (net (code "18") (name "/STR_IHM_SW_Color") (class "Default")
      (node (ref "STR_RpuBPD6") (pin "1") (pinfunction "1_1") (pintype "passive"))
      (node (ref "STR_RsBPD6") (pin "1") (pinfunction "1_1") (pintype "passive"))
    )
    (net (code "19") (name "/STR_IHM_SW_LCD") (class "Default")
      (node (ref "STR_RpuBPE7") (pin "1") (pinfunction "1_1") (pintype "passive"))
      (node (ref "STR_RsBPE7") (pin "1") (pinfunction "1_1") (pintype "passive"))
    )
    (net (code "20") (name "/STR_PA0_BP_Run_Match") (class "Default")
      (node (ref "STR_STM32F4DISCOVERY") (pin "12") (pinfunction "PA0-WKUP/USART2_CTS/USART4_TX/ETH_MII_CRS/TIM2_CH1_ETR/TIM5_CH1/TIM8_ETR/ADC123_IN0/WKUP_12") (pintype "passive"))
    )
    (net (code "21") (name "/STR_PA1_SW_Debug") (class "Default")
      (node (ref "STR_CfSWA1") (pin "2") (pinfunction "2_2") (pintype "passive"))
      (node (ref "STR_RsSWA1") (pin "2") (pinfunction "2_2") (pintype "passive"))
      (node (ref "STR_STM32F4DISCOVERY") (pin "11") (pinfunction "PA1/USART2_RTS/USART4_RX/ETH_RMII_REF_CLK/ETH_MII_RX_CLK/TIM5_CH2/TIMM2_CH2/ADC123_IN1_11") (pintype "passive"))
    )
    (net (code "22") (name "/STR_PA2_XBEE_TX") (class "Default")
      (node (ref "STR_STM32F4DISCOVERY") (pin "14") (pinfunction "PA2/USART2_TX/TIM5_CH3/TIM9_CH1/TIM2_CH3/ETH_MDIO/ADC123_IN2_14") (pintype "passive"))
    )
    (net (code "23") (name "/STR_PA3_XBEE_RX") (class "Default")
      (node (ref "STR_STM32F4DISCOVERY") (pin "13") (pinfunction "PA3/USART2_RX/TIM5_CH4/TIM9_CH2/TIM2_CH4/OTG_HS_ULPI_D0/ETH_MII_COL/ADC123_IN3_13") (pintype "passive"))
    )
    (net (code "24") (name "/STR_PA5_RF_XBEE_RESET") (class "Default")
      (node (ref "STR_STM32F4DISCOVERY") (pin "15") (pinfunction "PA5/SPI1_SCK/OTG_HS_ULPI_CK/TIM2_CH1_ETR/TIM8_CHIN/ADC12_IN5/DAC2_OUT_15") (pintype "passive"))
    )
    (net (code "25") (name "/STR_PA6_RF_Config") (class "Default")
      (node (ref "STR_STM32F4DISCOVERY") (pin "18") (pinfunction "PA6/SPI1_MISO/TIM8_BKIN/TIM13_CH1/DCMI_PIXCLK/TIM3_CH1/TIM1_BKIN/ADC12_IN6_18") (pintype "passive"))
    )
    (net (code "26") (name "/STR_PA7_SW_Verbose") (class "Default")
      (node (ref "STR_CfSWA7") (pin "2") (pinfunction "2_2") (pintype "passive"))
      (node (ref "STR_RsSWA7") (pin "2") (pinfunction "2_2") (pintype "passive"))
      (node (ref "STR_STM32F4DISCOVERY") (pin "17") (pinfunction "PA7/SPI1_MOSI/TIM8_CH1N/TIM14_CH1TIM3_CH2/ETH_MII_RX_DV/TIM1_CH1N/RMII_CRS_DV/ADC12_IN7_17") (pintype "passive"))
    )
    (net (code "27") (name "/STR_PA8_LED_IHM_Set") (class "Default")
      (node (ref "STR_RsLedA8") (pin "1") (pinfunction "1_1") (pintype "passive"))
      (node (ref "STR_STM32F4DISCOVERY") (pin "93") (pinfunction "PA8/MCO1/USART1_CK/TIM1_CH1/I2C3_SCL/OTG_FS_SOF_93") (pintype "passive"))
    )
    (net (code "28") (name "/STR_PA15_BP_Print_Match") (class "Default")
      (node (ref "STR_CfBPA15") (pin "2") (pinfunction "2_2") (pintype "passive"))
      (node (ref "STR_RsBPA15") (pin "2") (pinfunction "2_2") (pintype "passive"))
      (node (ref "STR_STM32F4DISCOVERY") (pin "90") (pinfunction "PA15/JTDI/SPI3_NSS/I2S3_WS/TIM2_CH1_ETR/SPI1_NSS_90") (pintype "passive"))
    )
    (net (code "29") (name "/STR_PB0_MESURE_24V") (class "Default")
      (node (ref "STR_Cmes24") (pin "2") (pinfunction "2_2") (pintype "passive"))
      (node (ref "STR_Rsmed24") (pin "2") (pinfunction "2_2") (pintype "passive"))
      (node (ref "STR_STM32F4DISCOVERY") (pin "22") (pinfunction "PB0/TIM3_CH3/TIM8_CH2N/OTG_HS_ULPI_D1/ETH_MII_RXD2/TIM1_CH2N/ADC12_IN8_22") (pintype "passive"))
    )
    (net (code "30") (name "/STR_PB1_Capteur") (class "Default")
      (node (ref "STR_CfDTb1") (pin "2") (pinfunction "2_2") (pintype "passive"))
      (node (ref "STR_RfDTb1") (pin "2") (pinfunction "2_2") (pintype "passive"))
      (node (ref "STR_STM32F4DISCOVERY") (pin "21") (pinfunction "PB1/TIM3_CH4/TIM_CH3N/OTG_HS_ULPI_D2/ETH_MII_RXD3/OTG_HS_INTN/TIM1_CH3N/ADC12_IN9_21") (pintype "passive"))
    )
    (net (code "31") (name "/STR_PB2_RFU") (class "Default")
      (node (ref "STR_STM32F4DISCOVERY") (pin "24") (pinfunction "PB2_24") (pintype "passive"))
    )
    (net (code "32") (name "/STR_PB4_SW_XBee_ON{slash}OFF") (class "Default")
      (node (ref "STR_CfSWB4") (pin "2") (pinfunction "2_2") (pintype "passive"))
      (node (ref "STR_RsSWB4") (pin "2") (pinfunction "2_2") (pintype "passive"))
      (node (ref "STR_STM32F4DISCOVERY") (pin "75") (pinfunction "PB4/NJTRST/SPI3_MISO/TIM3_CH1/SPI1_MISO/I2S3ext_SD_75") (pintype "passive"))
    )
    (net (code "33") (name "/STR_PB5_SW_Save_ON{slash}OFF") (class "Default")
      (node (ref "STR_CfSWB5") (pin "2") (pinfunction "2_2") (pintype "passive"))
      (node (ref "STR_RsSWB5") (pin "2") (pinfunction "2_2") (pintype "passive"))
      (node (ref "STR_STM32F4DISCOVERY") (pin "76") (pinfunction "PB5/I2C1_SMBA/CAN2_RX/OTG_HS_ULPI_D7/ETH_PPS_OUT/TIM3_CH2/SPI1_MOSI/SPI3_MOSI/DCMI_D10/I2S3_SD_76") (pintype "passive"))
    )
    (net (code "34") (name "/STR_PB6_U1TX") (class "Default")
      (node (ref "STR_RsU1tx") (pin "2") (pinfunction "2_2") (pintype "passive"))
      (node (ref "STR_STM32F4DISCOVERY") (pin "73") (pinfunction "PB6/I2C1_SCL/TIM4_CH1/CAN2_TX/OTG_FS_INTN/DCMI_D5/USART1_TX_73") (pintype "passive"))
    )
    (net (code "35") (name "/STR_PB7_U1RX") (class "Default")
      (node (ref "STR_Cu1rx") (pin "2") (pinfunction "2_2") (pintype "passive"))
      (node (ref "STR_RpuU1rx") (pin "1") (pinfunction "1_1") (pintype "passive"))
      (node (ref "STR_Rsu1rx") (pin "1") (pinfunction "1_1") (pintype "passive"))
      (node (ref "STR_STM32F4DISCOVERY") (pin "74") (pinfunction "PB7/I2C1_SDA/FSMC_ML/DCMI_VSYNC/USART1_RX/TIM4_CH2_74") (pintype "passive"))
    )
    (net (code "36") (name "/STR_PB10_SCL") (class "Default")
      (node (ref "STR_RTC") (pin "6") (pinfunction "SCL_6") (pintype "input"))
      (node (ref "STR_Rscl") (pin "1") (pinfunction "1_1") (pintype "passive"))
      (node (ref "STR_STM32F4DISCOVERY") (pin "34") (pinfunction "PB10/SPI2_SCK/I2S2_CK/I2C2_SCL/USART3_TX/OTG_HS_ULPI_D3/ETH_MII_RX_ER/OTG_HS_SCL/TIM2_CH3_34") (pintype "passive"))
    )
    (net (code "37") (name "/STR_PB11_SDA") (class "Default")
      (node (ref "STR_RTC") (pin "5") (pinfunction "SDA_5") (pintype "bidirectional"))
      (node (ref "STR_Rsda") (pin "1") (pinfunction "1_1") (pintype "passive"))
      (node (ref "STR_STM32F4DISCOVERY") (pin "35") (pinfunction "PB11/I2C2_SDA/USART3_RX/OTG_HS_ULPI_D4/ETH_RMII_TX_EN/ETH_MII_TX_EN/OTG_HS_SDA/TIM2_CH4_35") (pintype "passive"))
    )
    (net (code "38") (name "/STR_PB12_SD_CS") (class "Default")
      (node (ref "STR_RpudCs") (pin "2") (pinfunction "2_2") (pintype "passive"))
      (node (ref "STR_RsdCS") (pin "1") (pinfunction "1_1") (pintype "passive"))
      (node (ref "STR_STM32F4DISCOVERY") (pin "36") (pinfunction "PB12/SPI2_NSS/I2S2_WS/I2C2_SMBA/USART3_CK/TIM1_BKIN/CAN2_RX/OTG_HS_ULPI_D5/ETH_RMII_TXD0/ETH_MII_TXD0/OTG_HS_ID_36") (pintype "passive"))
    )
    (net (code "39") (name "/STR_PB13_SD_SCK") (class "Default")
      (node (ref "STR_RpudSck") (pin "1") (pinfunction "1_1") (pintype "passive"))
      (node (ref "STR_RsdSck") (pin "1") (pinfunction "1_1") (pintype "passive"))
      (node (ref "STR_STM32F4DISCOVERY") (pin "37") (pinfunction "PB13/SPI2_SCK/I2S2_CK/USART3_CTS/TIM1_CH1N/CAN2_TX/OTG_HS_ULPI_D6/ETH_RMII_TXD1/ETH_MII_TXD1/OTG_HS_VBUS_37") (pintype "passive"))
    )
    (net (code "40") (name "/STR_PB14_SD_MISO") (class "Default")
      (node (ref "STR_RpudMiso") (pin "1") (pinfunction "1_1") (pintype "passive"))
      (node (ref "STR_RsdMiso") (pin "1") (pinfunction "1_1") (pintype "passive"))
      (node (ref "STR_STM32F4DISCOVERY") (pin "38") (pinfunction "PB14/SPI2_MISO/TIM1_CH2N/TIM12_CH1/OTG_HS_DMUSART3_RTS/TIM8_CH2N/I2S2ext_SD_38") (pintype "passive"))
    )
    (net (code "41") (name "/STR_PB15_SD_MOSI") (class "Default")
      (node (ref "STR_RpudMosi") (pin "2") (pinfunction "2_2") (pintype "passive"))
      (node (ref "STR_RsdMosi") (pin "1") (pinfunction "1_1") (pintype "passive"))
      (node (ref "STR_STM32F4DISCOVERY") (pin "39") (pinfunction "PB15/SPI2_MOSI/I2S2_SD/TIM1_CH3N/TIM8_CH3N/TIM12_CH2/OTG_HS_DP_39") (pintype "passive"))
    )
    (net (code "42") (name "/STR_PC1_Capteur") (class "Default")
      (node (ref "STR_CfDTc1") (pin "2") (pinfunction "2_2") (pintype "passive"))
      (node (ref "STR_RfDTc1") (pin "2") (pinfunction "2_2") (pintype "passive"))
      (node (ref "STR_STM32F4DISCOVERY") (pin "7") (pinfunction "PC1/ETH_MDC/ADC123_IN11_7") (pintype "passive"))
    )
    (net (code "43") (name "/STR_PC2_Capteur") (class "Default")
      (node (ref "STR_CfDTc2") (pin "2") (pinfunction "2_2") (pintype "passive"))
      (node (ref "STR_RfDTc2") (pin "2") (pinfunction "2_2") (pintype "passive"))
      (node (ref "STR_STM32F4DISCOVERY") (pin "10") (pinfunction "PC2/SPI2_MISO/OTG_HS_ULPI_DIR/TH_MII_TXD2/I2S2ext_SD/ADC123_IN12_10") (pintype "passive"))
    )
    (net (code "44") (name "/STR_PC3_Capteur") (class "Default")
      (node (ref "STR_CfDTc3") (pin "2") (pinfunction "2_2") (pintype "passive"))
      (node (ref "STR_RfDTc3") (pin "2") (pinfunction "2_2") (pintype "passive"))
      (node (ref "STR_STM32F4DISCOVERY") (pin "9") (pinfunction "PC3/SPI2_MOSI/I2S2_SD/OTG_HS_ULPI_NXT/ETH_MII_TX_CLK/ADC123_IN13_9") (pintype "passive"))
    )
    (net (code "45") (name "/STR_PC4_Capteur") (class "Default")
      (node (ref "STR_CfDTc4") (pin "2") (pinfunction "2_2") (pintype "passive"))
      (node (ref "STR_RfDTc4") (pin "2") (pinfunction "2_2") (pintype "passive"))
      (node (ref "STR_STM32F4DISCOVERY") (pin "20") (pinfunction "PC4/ETH_RMII_RX_D0/ETH_MII_RX_D0/ADC12_IN14_20") (pintype "passive"))
    )
    (net (code "46") (name "/STR_PC5_BP_Set") (class "Default")
      (node (ref "STR_CfBPC5") (pin "2") (pinfunction "2_2") (pintype "passive"))
      (node (ref "STR_RsBPC5") (pin "2") (pinfunction "2_2") (pintype "passive"))
      (node (ref "STR_STM32F4DISCOVERY") (pin "19") (pinfunction "PC5/ETH_RMII_RX_D1/ETH_MII_RX_D1/ADC12_IN15_19") (pintype "passive"))
    )
    (net (code "47") (name "/STR_PC6_LED_Beacon_1_G") (class "Default")
      (node (ref "STR_RledC6") (pin "1") (pinfunction "1_1") (pintype "passive"))
      (node (ref "STR_STM32F4DISCOVERY") (pin "97") (pinfunction "PC6/I2S2_MCK/TIM8_CH1/SDIO_D6/USART6_TX/DCMI_D0/TIM3_CH1_97") (pintype "passive"))
    )
    (net (code "48") (name "/STR_PC7_LED_Beacon_1_R") (class "Default")
      (node (ref "STR_RledC7") (pin "1") (pinfunction "1_1") (pintype "passive"))
      (node (ref "STR_STM32F4DISCOVERY") (pin "98") (pinfunction "PC7/I2S3_MCK/TIM8_CH2/SDIO_D7/USART6_RX_DCMI_D1/TIM3_CH2_98") (pintype "passive"))
    )
    (net (code "49") (name "/STR_PC8_SynchroBalise") (class "Default")
      (node (ref "STR_STM32F4DISCOVERY") (pin "95") (pinfunction "PC8/TIM8_CH3/SDIO_D0/TIM3_CH3/USART6_CK/DCMI_D2_95") (pintype "passive"))
    )
    (net (code "50") (name "/STR_PC9_buzzer") (class "Default")
      (node (ref "STR_RsBuz") (pin "1") (pinfunction "1_1") (pintype "passive"))
      (node (ref "STR_STM32F4DISCOVERY") (pin "96") (pinfunction "PC9/I2S_CKIN/MCO2/TIM8_CH4/SDIO_D1/I2C3_SDA/DCMI_D3/TIM3_CH4_96") (pintype "passive"))
    )
    (net (code "51") (name "/STR_PC10_LED_IHM_OK") (class "Default")
      (node (ref "STR_RsLedC10") (pin "1") (pinfunction "1_1") (pintype "passive"))
      (node (ref "STR_STM32F4DISCOVERY") (pin "87") (pinfunction "PC10/SPI3_SCK/I2S3_CK/UART4_TX/SDIO_D2/DCMI_D8/USART3_TX_87") (pintype "passive"))
    )
    (net (code "52") (name "/STR_PC11_LED_IHM_+") (class "Default")
      (node (ref "STR_RsLedC11") (pin "1") (pinfunction "1_1") (pintype "passive"))
      (node (ref "STR_STM32F4DISCOVERY") (pin "88") (pinfunction "PC11/UART4_RX/SPI3_MISO/SDIO_D3/DCMI_D4/USART3_RX/I2S3ext_SD_88") (pintype "passive"))
    )
    (net (code "53") (name "/STR_PC12_LED_IHM_-") (class "Default")
      (node (ref "STR_RsLedC12") (pin "1") (pinfunction "1_1") (pintype "passive"))
      (node (ref "STR_STM32F4DISCOVERY") (pin "85") (pinfunction "PC12/UART5_TX/SDIO_CK/DCMI_D9/SPI3_MOSI/I2S3_SD/USART3_CK_85") (pintype "passive"))
    )
    (net (code "54") (name "/STR_PC13_WHO_AM_I") (class "Default")
      (node (ref "STR_RdwnWAmI") (pin "2") (pinfunction "2_2") (pintype "passive"))
      (node (ref "STR_RupWAmI") (pin "1") (pinfunction "1_1") (pintype "passive"))
      (node (ref "STR_STM32F4DISCOVERY") (pin "62") (pinfunction "PC13/RTC_AF1_62") (pintype "passive"))
    )
    (net (code "55") (name "/STR_PD0_CANRX") (class "Default")
      (node (ref "STR_STM32F4DISCOVERY") (pin "86") (pinfunction "PD0/FSMC_D2/CAN1_RX_86") (pintype "passive"))
      (node (ref "STR_Ucan") (pin "4") (pinfunction "RXD_4") (pintype "output"))
    )
    (net (code "56") (name "/STR_PD1_CANTX") (class "Default")
      (node (ref "STR_STM32F4DISCOVERY") (pin "83") (pinfunction "PD1/FSMC_D3/CAN1_TX_83") (pintype "passive"))
      (node (ref "STR_Ucan") (pin "1") (pinfunction "TXD_1") (pintype "input"))
    )
    (net (code "57") (name "/STR_PD2_LED_COLOR") (class "Default")
      (node (ref "STR_Qcolor2") (pin "1") (pinfunction "G_1") (pintype "passive"))
      (node (ref "STR_RpdColor2") (pin "2") (pinfunction "2_2") (pintype "passive"))
      (node (ref "STR_STM32F4DISCOVERY") (pin "84") (pinfunction "PD2/TIM3_ETR/UART5_RXSDIO_CMD/DCMI_D11_84") (pintype "passive"))
    )
    (net (code "58") (name "/STR_PD3_LED_COLOR") (class "Default")
      (node (ref "STR_Qcolor1") (pin "1") (pinfunction "G_1") (pintype "passive"))
      (node (ref "STR_RpdColor1") (pin "2") (pinfunction "2_2") (pintype "passive"))
      (node (ref "STR_STM32F4DISCOVERY") (pin "81") (pinfunction "PD3/FSMC_CLK/USART2_CTS_81") (pintype "passive"))
    )
    (net (code "59") (name "/STR_PD4_LED_COLOR") (class "Default")
      (node (ref "STR_Qcolor3") (pin "1") (pinfunction "G_1") (pintype "passive"))
      (node (ref "STR_RpdColor3") (pin "2") (pinfunction "2_2") (pintype "passive"))
      (node (ref "STR_STM32F4DISCOVERY") (pin "82") (pinfunction "PD4/FSMC_NOE/USART2_RTS_82") (pintype "passive"))
    )
    (net (code "60") (name "/STR_PD6_SW_Color") (class "Default")
      (node (ref "STR_CfBPD6") (pin "2") (pinfunction "2_2") (pintype "passive"))
      (node (ref "STR_RsBPD6") (pin "2") (pinfunction "2_2") (pintype "passive"))
      (node (ref "STR_STM32F4DISCOVERY") (pin "80") (pinfunction "PD6/FSMC_NWAIT/USART2_RX_80") (pintype "passive"))
    )
    (net (code "61") (name "/STR_PD7_Biroute") (class "Default")
      (node (ref "STR_CfBPD7") (pin "2") (pinfunction "2_2") (pintype "passive"))
      (node (ref "STR_RsBPD7") (pin "2") (pinfunction "2_2") (pintype "passive"))
      (node (ref "STR_STM32F4DISCOVERY") (pin "77") (pinfunction "PD7/USART2_CK/FSMC_NE1/FSMC_NCE2_77") (pintype "passive"))
    )
    (net (code "62") (name "/STR_PD8_RF_TX") (class "Default")
      (node (ref "STR_STM32F4DISCOVERY") (pin "40") (pinfunction "PD8/FSMC_D13/USART3_TX_40") (pintype "passive"))
    )
    (net (code "63") (name "/STR_PD9_RF_RX") (class "Default")
      (node (ref "STR_STM32F4DISCOVERY") (pin "41") (pinfunction "PD9/FSMC_D14/USART3_RX_41") (pintype "passive"))
    )
    (net (code "64") (name "/STR_PD10_ERROR") (class "Default")
      (node (ref "STR_Rderror") (pin "1") (pinfunction "1_1") (pintype "passive"))
      (node (ref "STR_STM32F4DISCOVERY") (pin "42") (pinfunction "PD10/FSMC_D15/USART3_CK_42") (pintype "passive"))
    )
    (net (code "65") (name "/STR_PD11_SELFTEST") (class "Default")
      (node (ref "STR_Rdselftest") (pin "1") (pinfunction "1_1") (pintype "passive"))
      (node (ref "STR_STM32F4DISCOVERY") (pin "43") (pinfunction "PD11/FSMC_A16/USART3_CTS_43") (pintype "passive"))
    )
    (net (code "66") (name "/STR_PD12_RUN") (class "Default")
      (node (ref "STR_Rdrun") (pin "1") (pinfunction "1_1") (pintype "passive"))
      (node (ref "STR_STM32F4DISCOVERY") (pin "44") (pinfunction "PD12/FSMC_A17/TIM4_CH1/USART3_RTS_44") (pintype "passive"))
    )
    (net (code "67") (name "/STR_PD13_CAN") (class "Default")
      (node (ref "STR_Rdcan") (pin "1") (pinfunction "1_1") (pintype "passive"))
      (node (ref "STR_STM32F4DISCOVERY") (pin "45") (pinfunction "PD13/FSMC_A18/TIM4_CH2_45") (pintype "passive"))
    )
    (net (code "68") (name "/STR_PD14_UART") (class "Default")
      (node (ref "STR_Rduart") (pin "1") (pinfunction "1_1") (pintype "passive"))
      (node (ref "STR_STM32F4DISCOVERY") (pin "46") (pinfunction "PD14/FSMC_D0/TIM4_CH3_46") (pintype "passive"))
    )
    (net (code "69") (name "/STR_PD15_USER") (class "Default")
      (node (ref "STR_Rduser") (pin "1") (pinfunction "1_1") (pintype "passive"))
      (node (ref "STR_STM32F4DISCOVERY") (pin "47") (pinfunction "PD15/FSMC_D1/TIM4_CH4_47") (pintype "passive"))
    )
    (net (code "70") (name "/STR_PE7_SW_LCD") (class "Default")
      (node (ref "STR_CfBPE7") (pin "2") (pinfunction "2_2") (pintype "passive"))
      (node (ref "STR_RsBPE7") (pin "2") (pinfunction "2_2") (pintype "passive"))
      (node (ref "STR_STM32F4DISCOVERY") (pin "25") (pinfunction "PE7/FSMC_D4/TIM1_ETR_25") (pintype "passive"))
    )
    (net (code "71") (name "/STR_PE8_SW_EVIT") (class "Default")
      (node (ref "STR_CfSWE8") (pin "2") (pinfunction "2_2") (pintype "passive"))
      (node (ref "STR_RsSWE8") (pin "2") (pinfunction "2_2") (pintype "passive"))
      (node (ref "STR_STM32F4DISCOVERY") (pin "26") (pinfunction "PE8/FSMC_D5/TIM1_CH1N_26") (pintype "passive"))
    )
    (net (code "72") (name "/STR_PE9_SW_STRAT1") (class "Default")
      (node (ref "STR_CfSWE9") (pin "2") (pinfunction "2_2") (pintype "passive"))
      (node (ref "STR_RsSWE9") (pin "2") (pinfunction "2_2") (pintype "passive"))
      (node (ref "STR_STM32F4DISCOVERY") (pin "27") (pinfunction "PE9/FSMC_D6/TIM1_CH1_27") (pintype "passive"))
    )
    (net (code "73") (name "/STR_PE10_SW _STRAT2") (class "Default")
      (node (ref "STR_CfSWE10") (pin "2") (pinfunction "2_2") (pintype "passive"))
      (node (ref "STR_RsSWE10") (pin "2") (pinfunction "2_2") (pintype "passive"))
      (node (ref "STR_STM32F4DISCOVERY") (pin "28") (pinfunction "PE10/FSMC_D7/TIM1_CH2N_28") (pintype "passive"))
    )
    (net (code "74") (name "/STR_PE11_SW_STRAT3") (class "Default")
      (node (ref "STR_CfSWE11") (pin "2") (pinfunction "2_2") (pintype "passive"))
      (node (ref "STR_RsSWE11") (pin "2") (pinfunction "2_2") (pintype "passive"))
      (node (ref "STR_STM32F4DISCOVERY") (pin "29") (pinfunction "PE11/FSMC_D8/TIM1_CH2_29") (pintype "passive"))
    )
    (net (code "75") (name "/STR_PE12_BP_Selftest") (class "Default")
      (node (ref "STR_CfBPE12") (pin "2") (pinfunction "2_2") (pintype "passive"))
      (node (ref "STR_RsBPE12") (pin "2") (pinfunction "2_2") (pintype "passive"))
      (node (ref "STR_STM32F4DISCOVERY") (pin "30") (pinfunction "PE12/FSMC_D9/TIM1_CH3N_30") (pintype "passive"))
    )
    (net (code "76") (name "/STR_PE13_BP_Menu_LCD_OK") (class "Default")
      (node (ref "STR_CfBPE13") (pin "2") (pinfunction "2_2") (pintype "passive"))
      (node (ref "STR_RsBPE13") (pin "2") (pinfunction "2_2") (pintype "passive"))
      (node (ref "STR_STM32F4DISCOVERY") (pin "31") (pinfunction "PE13/FSMC_D10/TIM1_CH3_31") (pintype "passive"))
    )
    (net (code "77") (name "/STR_PE14_BP_Menu_LCD+") (class "Default")
      (node (ref "STR_CfBPE14") (pin "2") (pinfunction "2_2") (pintype "passive"))
      (node (ref "STR_RsBPE14") (pin "2") (pinfunction "2_2") (pintype "passive"))
      (node (ref "STR_STM32F4DISCOVERY") (pin "32") (pinfunction "PE14/FSMC_D11/TIM1_CH4_32") (pintype "passive"))
    )
    (net (code "78") (name "/STR_PE15_BP_Menu_LCD-") (class "Default")
      (node (ref "STR_CfBPE15") (pin "2") (pinfunction "2_2") (pintype "passive"))
      (node (ref "STR_RsBPE15") (pin "2") (pinfunction "2_2") (pintype "passive"))
      (node (ref "STR_STM32F4DISCOVERY") (pin "33") (pinfunction "PE15/FSMC_D12/TIM1_BKIN_33") (pintype "passive"))
    )
    (net (code "79") (name "/STR_U1RX") (class "Default")
      (node (ref "STR_Rsu1rx") (pin "2") (pinfunction "2_2") (pintype "passive"))
      (node (ref "STR_UART1") (pin "4") (pinfunction "4_4") (pintype "passive"))
    )
    (net (code "80") (name "/STR_U1TX") (class "Default")
      (node (ref "STR_RpuU1tx") (pin "1") (pinfunction "1_1") (pintype "passive"))
      (node (ref "STR_RsU1tx") (pin "1") (pinfunction "1_1") (pintype "passive"))
      (node (ref "STR_UART1") (pin "3") (pinfunction "3_3") (pintype "passive"))
    )
    (net (code "81") (name "3V_STR") (class "Default")
      (node (ref "STR_Cd1SD") (pin "2") (pinfunction "2_2") (pintype "passive"))
      (node (ref "STR_Cd2SD") (pin "2") (pinfunction "2_2") (pintype "passive"))
      (node (ref "STR_MICRO_SD") (pin "4") (pinfunction "VDD_4") (pintype "passive"))
      (node (ref "STR_RpuBPA15") (pin "2") (pinfunction "2_2") (pintype "passive"))
      (node (ref "STR_RpuBPC5") (pin "2") (pinfunction "2_2") (pintype "passive"))
      (node (ref "STR_RpuBPD6") (pin "2") (pinfunction "2_2") (pintype "passive"))
      (node (ref "STR_RpuBPD7") (pin "2") (pinfunction "2_2") (pintype "passive"))
      (node (ref "STR_RpuBPE12") (pin "2") (pinfunction "2_2") (pintype "passive"))
      (node (ref "STR_RpuBPE13") (pin "2") (pinfunction "2_2") (pintype "passive"))
      (node (ref "STR_RpuBPE14") (pin "2") (pinfunction "2_2") (pintype "passive"))
      (node (ref "STR_RpuBPE15") (pin "2") (pinfunction "2_2") (pintype "passive"))
      (node (ref "STR_RpuBPE7") (pin "2") (pinfunction "2_2") (pintype "passive"))
      (node (ref "STR_RpuSB4") (pin "2") (pinfunction "2_2") (pintype "passive"))
      (node (ref "STR_RpuSWA1") (pin "2") (pinfunction "2_2") (pintype "passive"))
      (node (ref "STR_RpuSWA7") (pin "2") (pinfunction "2_2") (pintype "passive"))
      (node (ref "STR_RpuSWB5") (pin "2") (pinfunction "2_2") (pintype "passive"))
      (node (ref "STR_RpuSWE10") (pin "2") (pinfunction "2_2") (pintype "passive"))
      (node (ref "STR_RpuSWE11") (pin "2") (pinfunction "2_2") (pintype "passive"))
      (node (ref "STR_RpuSWE8") (pin "2") (pinfunction "2_2") (pintype "passive"))
      (node (ref "STR_RpuSWE9") (pin "2") (pinfunction "2_2") (pintype "passive"))
      (node (ref "STR_RpuU1rx") (pin "2") (pinfunction "2_2") (pintype "passive"))
      (node (ref "STR_RpuU1tx") (pin "2") (pinfunction "2_2") (pintype "passive"))
      (node (ref "STR_RpudCs") (pin "1") (pinfunction "1_1") (pintype "passive"))
      (node (ref "STR_RpudMiso") (pin "2") (pinfunction "2_2") (pintype "passive"))
      (node (ref "STR_RpudMosi") (pin "1") (pinfunction "1_1") (pintype "passive"))
      (node (ref "STR_RpudSck") (pin "2") (pinfunction "2_2") (pintype "passive"))
      (node (ref "STR_RupWAmI") (pin "2") (pinfunction "2_2") (pintype "passive"))
      (node (ref "STR_STM32F4DISCOVERY") (pin "55") (pinfunction "3V_55") (pintype "passive"))
      (node (ref "STR_STM32F4DISCOVERY") (pin "56") (pinfunction "3V_56") (pintype "passive"))
    )
    (net (code "82") (name "5V") (class "Default")
      (node (ref "STR_CdCan1") (pin "2") (pinfunction "2_2") (pintype "passive"))
      (node (ref "STR_CdCan2") (pin "2") (pinfunction "2_2") (pintype "passive"))
      (node (ref "STR_Cd_RTC") (pin "1") (pinfunction "1_1") (pintype "passive"))
      (node (ref "STR_RTC") (pin "8") (pinfunction "VCC_8") (pintype "power_in"))
      (node (ref "STR_Rscl") (pin "2") (pinfunction "2_2") (pintype "passive"))
      (node (ref "STR_Rsda") (pin "2") (pinfunction "2_2") (pintype "passive"))
      (node (ref "STR_STM32F4DISCOVERY") (pin "53") (pinfunction "5V_53") (pintype "passive"))
      (node (ref "STR_STM32F4DISCOVERY") (pin "54") (pinfunction "5V_54") (pintype "passive"))
      (node (ref "STR_Ucan") (pin "3") (pinfunction "VDD_3") (pintype "power_in"))
    )
    (net (code "83") (name "24V") (class "Default")
      (node (ref "STR_CdDtb1") (pin "2") (pinfunction "2_2") (pintype "passive"))
      (node (ref "STR_CdDtc1") (pin "2") (pinfunction "2_2") (pintype "passive"))
      (node (ref "STR_CdDtc2") (pin "2") (pinfunction "2_2") (pintype "passive"))
      (node (ref "STR_CdDtc3") (pin "2") (pinfunction "2_2") (pintype "passive"))
      (node (ref "STR_CdDtc4") (pin "2") (pinfunction "2_2") (pintype "passive"))
      (node (ref "STR_DTb1") (pin "3") (pinfunction "3_3") (pintype "passive"))
      (node (ref "STR_DTc1") (pin "3") (pinfunction "3_3") (pintype "passive"))
      (node (ref "STR_DTc2") (pin "3") (pinfunction "3_3") (pintype "passive"))
      (node (ref "STR_DTc3") (pin "3") (pinfunction "3_3") (pintype "passive"))
      (node (ref "STR_DTc4") (pin "3") (pinfunction "3_3") (pintype "passive"))
      (node (ref "STR_mes24+") (pin "2") (pinfunction "2_2") (pintype "passive"))
    )
    (net (code "84") (name "GND") (class "Default")
      (node (ref "STR_Buz") (pin "2") (pinfunction "2_2") (pintype "passive"))
      (node (ref "STR_CR2032") (pin "2") (pinfunction "-_2") (pintype "power_in"))
      (node (ref "STR_Cd1SD") (pin "1") (pinfunction "1_1") (pintype "passive"))
      (node (ref "STR_Cd2SD") (pin "1") (pinfunction "1_1") (pintype "passive"))
      (node (ref "STR_CdCan1") (pin "1") (pinfunction "1_1") (pintype "passive"))
      (node (ref "STR_CdCan2") (pin "1") (pinfunction "1_1") (pintype "passive"))
      (node (ref "STR_Cd_RTC") (pin "2") (pinfunction "2_2") (pintype "passive"))
      (node (ref "STR_CfBPA15") (pin "1") (pinfunction "1_1") (pintype "passive"))
      (node (ref "STR_CfBPC5") (pin "1") (pinfunction "1_1") (pintype "passive"))
      (node (ref "STR_CfBPD6") (pin "1") (pinfunction "1_1") (pintype "passive"))
      (node (ref "STR_CfBPD7") (pin "1") (pinfunction "1_1") (pintype "passive"))
      (node (ref "STR_CfBPE12") (pin "1") (pinfunction "1_1") (pintype "passive"))
      (node (ref "STR_CfBPE13") (pin "1") (pinfunction "1_1") (pintype "passive"))
      (node (ref "STR_CfBPE14") (pin "1") (pinfunction "1_1") (pintype "passive"))
      (node (ref "STR_CfBPE15") (pin "1") (pinfunction "1_1") (pintype "passive"))
      (node (ref "STR_CfBPE7") (pin "1") (pinfunction "1_1") (pintype "passive"))
      (node (ref "STR_CfDTb1") (pin "1") (pinfunction "1_1") (pintype "passive"))
      (node (ref "STR_CfDTc1") (pin "1") (pinfunction "1_1") (pintype "passive"))
      (node (ref "STR_CfDTc2") (pin "1") (pinfunction "1_1") (pintype "passive"))
      (node (ref "STR_CfDTc3") (pin "1") (pinfunction "1_1") (pintype "passive"))
      (node (ref "STR_CfDTc4") (pin "1") (pinfunction "1_1") (pintype "passive"))
      (node (ref "STR_CfSWA1") (pin "1") (pinfunction "1_1") (pintype "passive"))
      (node (ref "STR_CfSWA7") (pin "1") (pinfunction "1_1") (pintype "passive"))
      (node (ref "STR_CfSWB4") (pin "1") (pinfunction "1_1") (pintype "passive"))
      (node (ref "STR_CfSWB5") (pin "1") (pinfunction "1_1") (pintype "passive"))
      (node (ref "STR_CfSWE10") (pin "1") (pinfunction "1_1") (pintype "passive"))
      (node (ref "STR_CfSWE11") (pin "1") (pinfunction "1_1") (pintype "passive"))
      (node (ref "STR_CfSWE8") (pin "1") (pinfunction "1_1") (pintype "passive"))
      (node (ref "STR_CfSWE9") (pin "1") (pinfunction "1_1") (pintype "passive"))
      (node (ref "STR_Cmes24") (pin "1") (pinfunction "1_1") (pintype "passive"))
      (node (ref "STR_Cu1rx") (pin "1") (pinfunction "1_1") (pintype "passive"))
      (node (ref "STR_DSelftest") (pin "2") (pinfunction "K_2") (pintype "passive"))
      (node (ref "STR_Dbuz") (pin "3") (pinfunction "A_3") (pintype "passive"))
      (node (ref "STR_Dc6") (pin "2") (pinfunction "K_2") (pintype "passive"))
      (node (ref "STR_Dc7") (pin "2") (pinfunction "K_2") (pintype "passive"))
      (node (ref "STR_Dcan") (pin "2") (pinfunction "K_2") (pintype "passive"))
      (node (ref "STR_Derror") (pin "2") (pinfunction "K_2") (pintype "passive"))
      (node (ref "STR_Drun") (pin "2") (pinfunction "K_2") (pintype "passive"))
      (node (ref "STR_Duart") (pin "2") (pinfunction "K_2") (pintype "passive"))
      (node (ref "STR_Duser") (pin "2") (pinfunction "K_2") (pintype "passive"))
      (node (ref "STR_MICRO_SD") (pin "0") (pinfunction "CAP_0") (pintype "passive"))
      (node (ref "STR_MICRO_SD") (pin "6") (pinfunction "VSS_6") (pintype "passive"))
      (node (ref "STR_MICRO_SD") (pin "9") (pinfunction "Nail_Gnd_9") (pintype "passive"))
      (node (ref "STR_Qcolor1") (pin "2") (pinfunction "S_2") (pintype "passive"))
      (node (ref "STR_Qcolor2") (pin "2") (pinfunction "S_2") (pintype "passive"))
      (node (ref "STR_Qcolor3") (pin "2") (pinfunction "S_2") (pintype "passive"))
      (node (ref "STR_RTC") (pin "4") (pinfunction "GND_4") (pintype "power_in"))
      (node (ref "STR_Rdtb1") (pin "1") (pinfunction "1_1") (pintype "passive"))
      (node (ref "STR_Rdtc1") (pin "1") (pinfunction "1_1") (pintype "passive"))
      (node (ref "STR_Rdtc2") (pin "1") (pinfunction "1_1") (pintype "passive"))
      (node (ref "STR_Rdtc3") (pin "1") (pinfunction "1_1") (pintype "passive"))
      (node (ref "STR_Rdtc4") (pin "1") (pinfunction "1_1") (pintype "passive"))
      (node (ref "STR_RdwnWAmI") (pin "1") (pinfunction "1_1") (pintype "passive"))
      (node (ref "STR_RpdColor1") (pin "1") (pinfunction "1_1") (pintype "passive"))
      (node (ref "STR_RpdColor2") (pin "1") (pinfunction "1_1") (pintype "passive"))
      (node (ref "STR_RpdColor3") (pin "1") (pinfunction "1_1") (pintype "passive"))
      (node (ref "STR_STM32F4DISCOVERY") (pin "1") (pinfunction "GND_1") (pintype "passive"))
      (node (ref "STR_STM32F4DISCOVERY") (pin "100") (pinfunction "GND_100") (pintype "passive"))
      (node (ref "STR_STM32F4DISCOVERY") (pin "2") (pinfunction "GND_2") (pintype "passive"))
      (node (ref "STR_STM32F4DISCOVERY") (pin "23") (pinfunction "GND_23") (pintype "passive"))
      (node (ref "STR_STM32F4DISCOVERY") (pin "49") (pinfunction "GND_49") (pintype "passive"))
      (node (ref "STR_STM32F4DISCOVERY") (pin "5") (pinfunction "GND_5") (pintype "passive"))
      (node (ref "STR_STM32F4DISCOVERY") (pin "50") (pinfunction "GND_50") (pintype "passive"))
      (node (ref "STR_STM32F4DISCOVERY") (pin "51") (pinfunction "GND_51") (pintype "passive"))
      (node (ref "STR_STM32F4DISCOVERY") (pin "52") (pinfunction "GND_52") (pintype "passive"))
      (node (ref "STR_STM32F4DISCOVERY") (pin "99") (pinfunction "GND_99") (pintype "passive"))
      (node (ref "STR_SWA1") (pin "COMMON1") (pinfunction "COMMON1_COMMON1") (pintype "passive"))
      (node (ref "STR_SWA7") (pin "COMMON1") (pinfunction "COMMON1_COMMON1") (pintype "passive"))
      (node (ref "STR_SWB4") (pin "COMMON1") (pinfunction "COMMON1_COMMON1") (pintype "passive"))
      (node (ref "STR_SWB5") (pin "COMMON1") (pinfunction "COMMON1_COMMON1") (pintype "passive"))
      (node (ref "STR_SWE10") (pin "COMMON1") (pinfunction "COMMON1_COMMON1") (pintype "passive"))
      (node (ref "STR_SWE11") (pin "COMMON1") (pinfunction "COMMON1_COMMON1") (pintype "passive"))
      (node (ref "STR_SWE8") (pin "COMMON1") (pinfunction "COMMON1_COMMON1") (pintype "passive"))
      (node (ref "STR_SWE9") (pin "COMMON1") (pinfunction "COMMON1_COMMON1") (pintype "passive"))
      (node (ref "STR_UART1") (pin "5") (pinfunction "5_5") (pintype "passive"))
      (node (ref "STR_UART1") (pin "6") (pinfunction "6_6") (pintype "passive"))
      (node (ref "STR_Ucan") (pin "2") (pinfunction "VSS_2") (pintype "power_in"))
      (node (ref "STR_Ucan") (pin "8") (pinfunction "RS_8") (pintype "input"))
    )
    (net (code "85") (name "GND_24") (class "Default")
      (node (ref "STR_CdDtb1") (pin "1") (pinfunction "1_1") (pintype "passive"))
      (node (ref "STR_CdDtc1") (pin "1") (pinfunction "1_1") (pintype "passive"))
      (node (ref "STR_CdDtc2") (pin "1") (pinfunction "1_1") (pintype "passive"))
      (node (ref "STR_CdDtc3") (pin "1") (pinfunction "1_1") (pintype "passive"))
      (node (ref "STR_CdDtc4") (pin "1") (pinfunction "1_1") (pintype "passive"))
      (node (ref "STR_DTb1") (pin "1") (pinfunction "1_1") (pintype "passive"))
      (node (ref "STR_DTc1") (pin "1") (pinfunction "1_1") (pintype "passive"))
      (node (ref "STR_DTc2") (pin "1") (pinfunction "1_1") (pintype "passive"))
      (node (ref "STR_DTc3") (pin "1") (pinfunction "1_1") (pintype "passive"))
      (node (ref "STR_DTc4") (pin "1") (pinfunction "1_1") (pintype "passive"))
      (node (ref "STR_mes24-") (pin "1") (pinfunction "1_1") (pintype "passive"))
    )
    (net (code "86") (name "Net-(STR_CR2032-+)") (class "Default")
      (node (ref "STR_CR2032") (pin "1") (pinfunction "+_1") (pintype "power_in"))
      (node (ref "STR_RTC") (pin "3") (pinfunction "VBAT_3") (pintype "power_in"))
    )
    (net (code "87") (name "Net-(STR_DSelftest-A)") (class "Default")
      (node (ref "STR_DSelftest") (pin "1") (pinfunction "A_1") (pintype "passive"))
      (node (ref "STR_Rdselftest") (pin "2") (pinfunction "2_2") (pintype "passive"))
    )
    (net (code "88") (name "Net-(STR_DTb1-Pad2)") (class "Default")
      (node (ref "STR_DTb1") (pin "2") (pinfunction "2_2") (pintype "passive"))
      (node (ref "STR_Rdtb1") (pin "2") (pinfunction "2_2") (pintype "passive"))
      (node (ref "STR_RfDTb1") (pin "1") (pinfunction "1_1") (pintype "passive"))
    )
    (net (code "89") (name "Net-(STR_DTc1-Pad2)") (class "Default")
      (node (ref "STR_DTc1") (pin "2") (pinfunction "2_2") (pintype "passive"))
      (node (ref "STR_Rdtc1") (pin "2") (pinfunction "2_2") (pintype "passive"))
      (node (ref "STR_RfDTc1") (pin "1") (pinfunction "1_1") (pintype "passive"))
    )
    (net (code "90") (name "Net-(STR_DTc2-Pad2)") (class "Default")
      (node (ref "STR_DTc2") (pin "2") (pinfunction "2_2") (pintype "passive"))
      (node (ref "STR_Rdtc2") (pin "2") (pinfunction "2_2") (pintype "passive"))
      (node (ref "STR_RfDTc2") (pin "1") (pinfunction "1_1") (pintype "passive"))
    )
    (net (code "91") (name "Net-(STR_DTc3-Pad2)") (class "Default")
      (node (ref "STR_DTc3") (pin "2") (pinfunction "2_2") (pintype "passive"))
      (node (ref "STR_Rdtc3") (pin "2") (pinfunction "2_2") (pintype "passive"))
      (node (ref "STR_RfDTc3") (pin "1") (pinfunction "1_1") (pintype "passive"))
    )
    (net (code "92") (name "Net-(STR_DTc4-Pad2)") (class "Default")
      (node (ref "STR_DTc4") (pin "2") (pinfunction "2_2") (pintype "passive"))
      (node (ref "STR_Rdtc4") (pin "2") (pinfunction "2_2") (pintype "passive"))
      (node (ref "STR_RfDTc4") (pin "1") (pinfunction "1_1") (pintype "passive"))
    )
    (net (code "93") (name "Net-(STR_Dbuz-K1)") (class "Default")
      (node (ref "STR_Buz") (pin "1") (pinfunction "1_1") (pintype "passive"))
      (node (ref "STR_Dbuz") (pin "1") (pinfunction "K1_1") (pintype "passive"))
      (node (ref "STR_Rvarbuz") (pin "3") (pinfunction "3_3") (pintype "passive"))
    )
    (net (code "94") (name "Net-(STR_Dc6-A)") (class "Default")
      (node (ref "STR_Dc6") (pin "1") (pinfunction "A_1") (pintype "passive"))
      (node (ref "STR_RledC6") (pin "2") (pinfunction "2_2") (pintype "passive"))
    )
    (net (code "95") (name "Net-(STR_Dc7-A)") (class "Default")
      (node (ref "STR_Dc7") (pin "1") (pinfunction "A_1") (pintype "passive"))
      (node (ref "STR_RledC7") (pin "2") (pinfunction "2_2") (pintype "passive"))
    )
    (net (code "96") (name "Net-(STR_Dcan-A)") (class "Default")
      (node (ref "STR_Dcan") (pin "1") (pinfunction "A_1") (pintype "passive"))
      (node (ref "STR_Rdcan") (pin "2") (pinfunction "2_2") (pintype "passive"))
    )
    (net (code "97") (name "Net-(STR_Derror-A)") (class "Default")
      (node (ref "STR_Derror") (pin "1") (pinfunction "A_1") (pintype "passive"))
      (node (ref "STR_Rderror") (pin "2") (pinfunction "2_2") (pintype "passive"))
    )
    (net (code "98") (name "Net-(STR_Drun-A)") (class "Default")
      (node (ref "STR_Drun") (pin "1") (pinfunction "A_1") (pintype "passive"))
      (node (ref "STR_Rdrun") (pin "2") (pinfunction "2_2") (pintype "passive"))
    )
    (net (code "99") (name "Net-(STR_Duart-A)") (class "Default")
      (node (ref "STR_Duart") (pin "1") (pinfunction "A_1") (pintype "passive"))
      (node (ref "STR_Rduart") (pin "2") (pinfunction "2_2") (pintype "passive"))
    )
    (net (code "100") (name "Net-(STR_Duser-A)") (class "Default")
      (node (ref "STR_Duser") (pin "1") (pinfunction "A_1") (pintype "passive"))
      (node (ref "STR_Rduser") (pin "2") (pinfunction "2_2") (pintype "passive"))
    )
    (net (code "101") (name "Net-(STR_MICRO_SD-CS)") (class "Default")
      (node (ref "STR_MICRO_SD") (pin "2") (pinfunction "CS_2") (pintype "passive"))
      (node (ref "STR_RsdCS") (pin "2") (pinfunction "2_2") (pintype "passive"))
    )
    (net (code "102") (name "Net-(STR_MICRO_SD-DI)") (class "Default")
      (node (ref "STR_MICRO_SD") (pin "3") (pinfunction "DI_3") (pintype "passive"))
      (node (ref "STR_RsdMosi") (pin "2") (pinfunction "2_2") (pintype "passive"))
    )
    (net (code "103") (name "Net-(STR_MICRO_SD-DO)") (class "Default")
      (node (ref "STR_MICRO_SD") (pin "7") (pinfunction "DO_7") (pintype "passive"))
      (node (ref "STR_RsdMiso") (pin "2") (pinfunction "2_2") (pintype "passive"))
    )
    (net (code "104") (name "Net-(STR_MICRO_SD-SCLK)") (class "Default")
      (node (ref "STR_MICRO_SD") (pin "5") (pinfunction "SCLK_5") (pintype "passive"))
      (node (ref "STR_RsdSck") (pin "2") (pinfunction "2_2") (pintype "passive"))
    )
    (net (code "105") (name "Net-(STR_Qcolor1-D)") (class "Default")
      (node (ref "STR_Qcolor1") (pin "3") (pinfunction "D_3") (pintype "passive"))
      (node (ref "STR_RledColor1") (pin "1") (pinfunction "1_1") (pintype "passive"))
    )
    (net (code "106") (name "Net-(STR_Qcolor2-D)") (class "Default")
      (node (ref "STR_Qcolor2") (pin "3") (pinfunction "D_3") (pintype "passive"))
      (node (ref "STR_RledColor2") (pin "1") (pinfunction "1_1") (pintype "passive"))
    )
    (net (code "107") (name "Net-(STR_Qcolor3-D)") (class "Default")
      (node (ref "STR_Qcolor3") (pin "3") (pinfunction "D_3") (pintype "passive"))
      (node (ref "STR_RledColor3") (pin "1") (pinfunction "1_1") (pintype "passive"))
    )
    (net (code "108") (name "Net-(STR_RTC-X1)") (class "Default")
      (node (ref "STR_Qz") (pin "1") (pinfunction "1_1") (pintype "passive"))
      (node (ref "STR_RTC") (pin "1") (pinfunction "X1_1") (pintype "input"))
    )
    (net (code "109") (name "Net-(STR_RTC-X2)") (class "Default")
      (node (ref "STR_Qz") (pin "4") (pinfunction "4_4") (pintype "passive"))
      (node (ref "STR_RTC") (pin "2") (pinfunction "X2_2") (pintype "input"))
    )
    (net (code "110") (name "Net-(STR_RpuSB4-Pad1)") (class "Default")
      (node (ref "STR_RpuSB4") (pin "1") (pinfunction "1_1") (pintype "passive"))
      (node (ref "STR_RsSWB4") (pin "1") (pinfunction "1_1") (pintype "passive"))
      (node (ref "STR_SWB4") (pin "NO1") (pinfunction "NO1_NO1") (pintype "passive"))
    )
    (net (code "111") (name "Net-(STR_RpuSWA1-Pad1)") (class "Default")
      (node (ref "STR_RpuSWA1") (pin "1") (pinfunction "1_1") (pintype "passive"))
      (node (ref "STR_RsSWA1") (pin "1") (pinfunction "1_1") (pintype "passive"))
      (node (ref "STR_SWA1") (pin "NO1") (pinfunction "NO1_NO1") (pintype "passive"))
    )
    (net (code "112") (name "Net-(STR_RpuSWA7-Pad1)") (class "Default")
      (node (ref "STR_RpuSWA7") (pin "1") (pinfunction "1_1") (pintype "passive"))
      (node (ref "STR_RsSWA7") (pin "1") (pinfunction "1_1") (pintype "passive"))
      (node (ref "STR_SWA7") (pin "NO1") (pinfunction "NO1_NO1") (pintype "passive"))
    )
    (net (code "113") (name "Net-(STR_RpuSWB5-Pad1)") (class "Default")
      (node (ref "STR_RpuSWB5") (pin "1") (pinfunction "1_1") (pintype "passive"))
      (node (ref "STR_RsSWB5") (pin "1") (pinfunction "1_1") (pintype "passive"))
      (node (ref "STR_SWB5") (pin "NO1") (pinfunction "NO1_NO1") (pintype "passive"))
    )
    (net (code "114") (name "Net-(STR_RpuSWE8-Pad1)") (class "Default")
      (node (ref "STR_RpuSWE8") (pin "1") (pinfunction "1_1") (pintype "passive"))
      (node (ref "STR_RsSWE8") (pin "1") (pinfunction "1_1") (pintype "passive"))
      (node (ref "STR_SWE8") (pin "NO1") (pinfunction "NO1_NO1") (pintype "passive"))
    )
    (net (code "115") (name "Net-(STR_RpuSWE9-Pad1)") (class "Default")
      (node (ref "STR_RpuSWE9") (pin "1") (pinfunction "1_1") (pintype "passive"))
      (node (ref "STR_RsSWE9") (pin "1") (pinfunction "1_1") (pintype "passive"))
      (node (ref "STR_SWE9") (pin "NO1") (pinfunction "NO1_NO1") (pintype "passive"))
    )
    (net (code "116") (name "Net-(STR_RpuSWE10-Pad1)") (class "Default")
      (node (ref "STR_RpuSWE10") (pin "1") (pinfunction "1_1") (pintype "passive"))
      (node (ref "STR_RsSWE10") (pin "1") (pinfunction "1_1") (pintype "passive"))
      (node (ref "STR_SWE10") (pin "NO1") (pinfunction "NO1_NO1") (pintype "passive"))
    )
    (net (code "117") (name "Net-(STR_RpuSWE11-Pad1)") (class "Default")
      (node (ref "STR_RpuSWE11") (pin "1") (pinfunction "1_1") (pintype "passive"))
      (node (ref "STR_RsSWE11") (pin "1") (pinfunction "1_1") (pintype "passive"))
      (node (ref "STR_SWE11") (pin "NO1") (pinfunction "NO1_NO1") (pintype "passive"))
    )
    (net (code "118") (name "Net-(STR_RsBuz-Pad2)") (class "Default")
      (node (ref "STR_RsBuz") (pin "2") (pinfunction "2_2") (pintype "passive"))
      (node (ref "STR_Rvarbuz") (pin "2") (pinfunction "2_2") (pintype "passive"))
    )
    (net (code "119") (name "Net-(STR_Rsmed24-Pad1)") (class "Default")
      (node (ref "STR_Rsmed24") (pin "1") (pinfunction "1_1") (pintype "passive"))
      (node (ref "STR_mes24+") (pin "1") (pinfunction "1_1") (pintype "passive"))
      (node (ref "STR_mes24-") (pin "2") (pinfunction "2_2") (pintype "passive"))
    )
    (net (code "120") (name "unconnected-(STR_Dbuz-K2-Pad2)") (class "Default")
      (node (ref "STR_Dbuz") (pin "2") (pinfunction "K2_2") (pintype "passive+no_connect"))
    )
    (net (code "121") (name "unconnected-(STR_MICRO_SD-Nail-Pad10)") (class "Default")
      (node (ref "STR_MICRO_SD") (pin "10") (pinfunction "Nail_10") (pintype "passive"))
    )
    (net (code "122") (name "unconnected-(STR_MICRO_SD-X-Pad1)") (class "Default")
      (node (ref "STR_MICRO_SD") (pin "1") (pinfunction "X_1") (pintype "passive+no_connect"))
    )
    (net (code "123") (name "unconnected-(STR_MICRO_SD-X-Pad8)") (class "Default")
      (node (ref "STR_MICRO_SD") (pin "8") (pinfunction "X_8") (pintype "passive+no_connect"))
    )
    (net (code "124") (name "unconnected-(STR_Qz-Pad2)") (class "Default")
      (node (ref "STR_Qz") (pin "2") (pinfunction "2_2") (pintype "passive"))
    )
    (net (code "125") (name "unconnected-(STR_Qz-Pad3)") (class "Default")
      (node (ref "STR_Qz") (pin "3") (pinfunction "3_3") (pintype "passive"))
    )
    (net (code "126") (name "unconnected-(STR_RTC-SQW{slash}OUT-Pad7)") (class "Default")
      (node (ref "STR_RTC") (pin "7") (pinfunction "SQW/OUT_7") (pintype "output+no_connect"))
    )
    (net (code "127") (name "unconnected-(STR_Rvarbuz-Pad1)") (class "Default")
      (node (ref "STR_Rvarbuz") (pin "1") (pinfunction "1_1") (pintype "passive+no_connect"))
    )
    (net (code "128") (name "unconnected-(STR_STM32F4DISCOVERY-BOOT0{slash}VPP-Pad71)") (class "Default")
      (node (ref "STR_STM32F4DISCOVERY") (pin "71") (pinfunction "BOOT0/VPP_71") (pintype "passive+no_connect"))
    )
    (net (code "129") (name "unconnected-(STR_STM32F4DISCOVERY-NC-Pad48)") (class "Default")
      (node (ref "STR_STM32F4DISCOVERY") (pin "48") (pinfunction "NC_48") (pintype "passive+no_connect"))
    )
    (net (code "130") (name "unconnected-(STR_STM32F4DISCOVERY-NRST-Pad6)") (class "Default")
      (node (ref "STR_STM32F4DISCOVERY") (pin "6") (pinfunction "NRST_6") (pintype "passive+no_connect"))
    )
    (net (code "131") (name "unconnected-(STR_STM32F4DISCOVERY-PA4{slash}SPI1_NSS{slash}SPI3_NSS{slash}USART2_CK{slash}DCMI_HSYNC{slash}OTG_HS_SOF{slash}I2S3_WS{slash}ADC12_IN4{slash}DAC1_OUT-Pad16)") (class "Default")
      (node (ref "STR_STM32F4DISCOVERY") (pin "16") (pinfunction "PA4/SPI1_NSS/SPI3_NSS/USART2_CK/DCMI_HSYNC/OTG_HS_SOF/I2S3_WS/ADC12_IN4/DAC1_OUT_16") (pintype "passive+no_connect"))
    )
    (net (code "132") (name "unconnected-(STR_STM32F4DISCOVERY-PA9{slash}USART1_TX{slash}TIM1_CH2{slash}I2C3_SMBA{slash}DCMI_D0{slash}OTG_FS_VBUS-Pad94)") (class "Default")
      (node (ref "STR_STM32F4DISCOVERY") (pin "94") (pinfunction "PA9/USART1_TX/TIM1_CH2/I2C3_SMBA/DCMI_D0/OTG_FS_VBUS_94") (pintype "passive+no_connect"))
    )
    (net (code "133") (name "unconnected-(STR_STM32F4DISCOVERY-PA10{slash}USART1_RX{slash}TIM1_CH3{slash}OTG_FS_ID{slash}DCMI_D1-Pad91)") (class "Default")
      (node (ref "STR_STM32F4DISCOVERY") (pin "91") (pinfunction "PA10/USART1_RX/TIM1_CH3/OTG_FS_ID/DCMI_D1_91") (pintype "passive+no_connect"))
    )
    (net (code "134") (name "unconnected-(STR_STM32F4DISCOVERY-PA13{slash}JTMS_SWDIO-Pad92)") (class "Default")
      (node (ref "STR_STM32F4DISCOVERY") (pin "92") (pinfunction "PA13/JTMS_SWDIO_92") (pintype "passive+no_connect"))
    )
    (net (code "135") (name "unconnected-(STR_STM32F4DISCOVERY-PA14{slash}JTCK_SWCLK-Pad89)") (class "Default")
      (node (ref "STR_STM32F4DISCOVERY") (pin "89") (pinfunction "PA14/JTCK_SWCLK_89") (pintype "passive+no_connect"))
    )
    (net (code "136") (name "unconnected-(STR_STM32F4DISCOVERY-PB3{slash}JTDO{slash}TRACESWO{slash}SPI3_SCK{slash}I2S3_CK{slash}TIM2_CH2{slash}SPI1_SCK-Pad78)") (class "Default")
      (node (ref "STR_STM32F4DISCOVERY") (pin "78") (pinfunction "PB3/JTDO/TRACESWO/SPI3_SCK/I2S3_CK/TIM2_CH2/SPI1_SCK_78") (pintype "passive+no_connect"))
    )
    (net (code "137") (name "unconnected-(STR_STM32F4DISCOVERY-PB8{slash}TIM4_CH3{slash}SDIO_D4{slash}TIM10_CH1{slash}DCMI_D6{slash}OTG_FS_SCL{slash}ETH_MII_TXD3{slash}I2C1_SCL{slash}CAN1_RX-Pad69)") (class "Default")
      (node (ref "STR_STM32F4DISCOVERY") (pin "69") (pinfunction "PB8/TIM4_CH3/SDIO_D4/TIM10_CH1/DCMI_D6/OTG_FS_SCL/ETH_MII_TXD3/I2C1_SCL/CAN1_RX_69") (pintype "passive+no_connect"))
    )
    (net (code "138") (name "unconnected-(STR_STM32F4DISCOVERY-PC0{slash}OTG_HS_ULPI_STP{slash}ADC123_IN10-Pad8)") (class "Default")
      (node (ref "STR_STM32F4DISCOVERY") (pin "8") (pinfunction "PC0/OTG_HS_ULPI_STP/ADC123_IN10_8") (pintype "passive+no_connect"))
    )
    (net (code "139") (name "unconnected-(STR_STM32F4DISCOVERY-PC14{slash}OSC32_IN-Pad59)") (class "Default")
      (node (ref "STR_STM32F4DISCOVERY") (pin "59") (pinfunction "PC14/OSC32_IN_59") (pintype "passive+no_connect"))
    )
    (net (code "140") (name "unconnected-(STR_STM32F4DISCOVERY-PC15{slash}OSC32_OUT-Pad60)") (class "Default")
      (node (ref "STR_STM32F4DISCOVERY") (pin "60") (pinfunction "PC15/OSC32_OUT_60") (pintype "passive+no_connect"))
    )
    (net (code "141") (name "unconnected-(STR_STM32F4DISCOVERY-PD5{slash}FSMC_NWE{slash}USART2_TX-Pad79)") (class "Default")
      (node (ref "STR_STM32F4DISCOVERY") (pin "79") (pinfunction "PD5/FSMC_NWE/USART2_TX_79") (pintype "passive+no_connect"))
    )
    (net (code "142") (name "unconnected-(STR_STM32F4DISCOVERY-PE0{slash}TIM4_ETR{slash}FSMC_NBL0{slash}DCMI_D2-Pad67)") (class "Default")
      (node (ref "STR_STM32F4DISCOVERY") (pin "67") (pinfunction "PE0/TIM4_ETR/FSMC_NBL0/DCMI_D2_67") (pintype "passive+no_connect"))
    )
    (net (code "143") (name "unconnected-(STR_STM32F4DISCOVERY-PE1{slash}FSMC_NBL1{slash}DCMI_D3-Pad68)") (class "Default")
      (node (ref "STR_STM32F4DISCOVERY") (pin "68") (pinfunction "PE1/FSMC_NBL1/DCMI_D3_68") (pintype "passive+no_connect"))
    )
    (net (code "144") (name "unconnected-(STR_STM32F4DISCOVERY-PE2{slash}TRACECLK{slash}FSMC_A23{slash}ETH_MII_TXD3-Pad65)") (class "Default")
      (node (ref "STR_STM32F4DISCOVERY") (pin "65") (pinfunction "PE2/TRACECLK/FSMC_A23/ETH_MII_TXD3_65") (pintype "passive+no_connect"))
    )
    (net (code "145") (name "unconnected-(STR_STM32F4DISCOVERY-PE3{slash}TRACED0{slash}FSMC_A19-Pad66)") (class "Default")
      (node (ref "STR_STM32F4DISCOVERY") (pin "66") (pinfunction "PE3/TRACED0/FSMC_A19_66") (pintype "passive+no_connect"))
    )
    (net (code "146") (name "unconnected-(STR_STM32F4DISCOVERY-PE4{slash}TRACED1{slash}FSMC_A20{slash}DCMI_D4-Pad63)") (class "Default")
      (node (ref "STR_STM32F4DISCOVERY") (pin "63") (pinfunction "PE4/TRACED1/FSMC_A20/DCMI_D4_63") (pintype "passive+no_connect"))
    )
    (net (code "147") (name "unconnected-(STR_STM32F4DISCOVERY-PE5{slash}TRACED2{slash}FSMC_A21{slash}TIM9_CH1{slash}DCMI_D6-Pad64)") (class "Default")
      (node (ref "STR_STM32F4DISCOVERY") (pin "64") (pinfunction "PE5/TRACED2/FSMC_A21/TIM9_CH1/DCMI_D6_64") (pintype "passive+no_connect"))
    )
    (net (code "148") (name "unconnected-(STR_STM32F4DISCOVERY-PE6{slash}TRACED3{slash}FSMC_A22{slash}TIM9_CH2{slash}DCMI_D7-Pad61)") (class "Default")
      (node (ref "STR_STM32F4DISCOVERY") (pin "61") (pinfunction "PE6/TRACED3/FSMC_A22/TIM9_CH2/DCMI_D7_61") (pintype "passive+no_connect"))
    )
    (net (code "149") (name "unconnected-(STR_STM32F4DISCOVERY-PH0{slash}OSC_IN-Pad57)") (class "Default")
      (node (ref "STR_STM32F4DISCOVERY") (pin "57") (pinfunction "PH0/OSC_IN_57") (pintype "passive+no_connect"))
    )
    (net (code "150") (name "unconnected-(STR_STM32F4DISCOVERY-PH1{slash}OSC_OUT-Pad58)") (class "Default")
      (node (ref "STR_STM32F4DISCOVERY") (pin "58") (pinfunction "PH1/OSC_OUT_58") (pintype "passive+no_connect"))
    )
    (net (code "151") (name "unconnected-(STR_STM32F4DISCOVERY-VDD-Pad3)") (class "Default")
      (node (ref "STR_STM32F4DISCOVERY") (pin "3") (pinfunction "VDD_3") (pintype "passive+no_connect"))
    )
    (net (code "152") (name "unconnected-(STR_STM32F4DISCOVERY-VDD-Pad4)") (class "Default")
      (node (ref "STR_STM32F4DISCOVERY") (pin "4") (pinfunction "VDD_4") (pintype "passive+no_connect"))
    )
    (net (code "153") (name "unconnected-(STR_STM32F4DISCOVERY-VDD-Pad72)") (class "Default")
      (node (ref "STR_STM32F4DISCOVERY") (pin "72") (pinfunction "VDD_72") (pintype "passive+no_connect"))
    )
    (net (code "154") (name "unconnected-(STR_SWA1-PadNC1)") (class "Default")
      (node (ref "STR_SWA1") (pin "NC1") (pinfunction "NC1_NC1") (pintype "passive+no_connect"))
    )
    (net (code "155") (name "unconnected-(STR_SWA7-PadNC1)") (class "Default")
      (node (ref "STR_SWA7") (pin "NC1") (pinfunction "NC1_NC1") (pintype "passive+no_connect"))
    )
    (net (code "156") (name "unconnected-(STR_SWB4-PadNC1)") (class "Default")
      (node (ref "STR_SWB4") (pin "NC1") (pinfunction "NC1_NC1") (pintype "passive+no_connect"))
    )
    (net (code "157") (name "unconnected-(STR_SWB5-PadNC1)") (class "Default")
      (node (ref "STR_SWB5") (pin "NC1") (pinfunction "NC1_NC1") (pintype "passive+no_connect"))
    )
    (net (code "158") (name "unconnected-(STR_SWE8-PadNC1)") (class "Default")
      (node (ref "STR_SWE8") (pin "NC1") (pinfunction "NC1_NC1") (pintype "passive+no_connect"))
    )
    (net (code "159") (name "unconnected-(STR_SWE9-PadNC1)") (class "Default")
      (node (ref "STR_SWE9") (pin "NC1") (pinfunction "NC1_NC1") (pintype "passive+no_connect"))
    )
    (net (code "160") (name "unconnected-(STR_SWE10-PadNC1)") (class "Default")
      (node (ref "STR_SWE10") (pin "NC1") (pinfunction "NC1_NC1") (pintype "passive+no_connect"))
    )
    (net (code "161") (name "unconnected-(STR_SWE11-PadNC1)") (class "Default")
      (node (ref "STR_SWE11") (pin "NC1") (pinfunction "NC1_NC1") (pintype "passive+no_connect"))
    )
    (net (code "162") (name "unconnected-(STR_UART1-Pad1)") (class "Default")
      (node (ref "STR_UART1") (pin "1") (pinfunction "1_1") (pintype "passive+no_connect"))
    )
    (net (code "163") (name "unconnected-(STR_UART1-Pad2)") (class "Default")
      (node (ref "STR_UART1") (pin "2") (pinfunction "2_2") (pintype "passive+no_connect"))
    )
    (net (code "164") (name "unconnected-(STR_Ucan-VREF-Pad5)") (class "Default")
      (node (ref "STR_Ucan") (pin "5") (pinfunction "VREF_5") (pintype "output"))
    )
  )
)
